# CPU-001.net
KiCad netlist of a schematic drawn in EAGLE
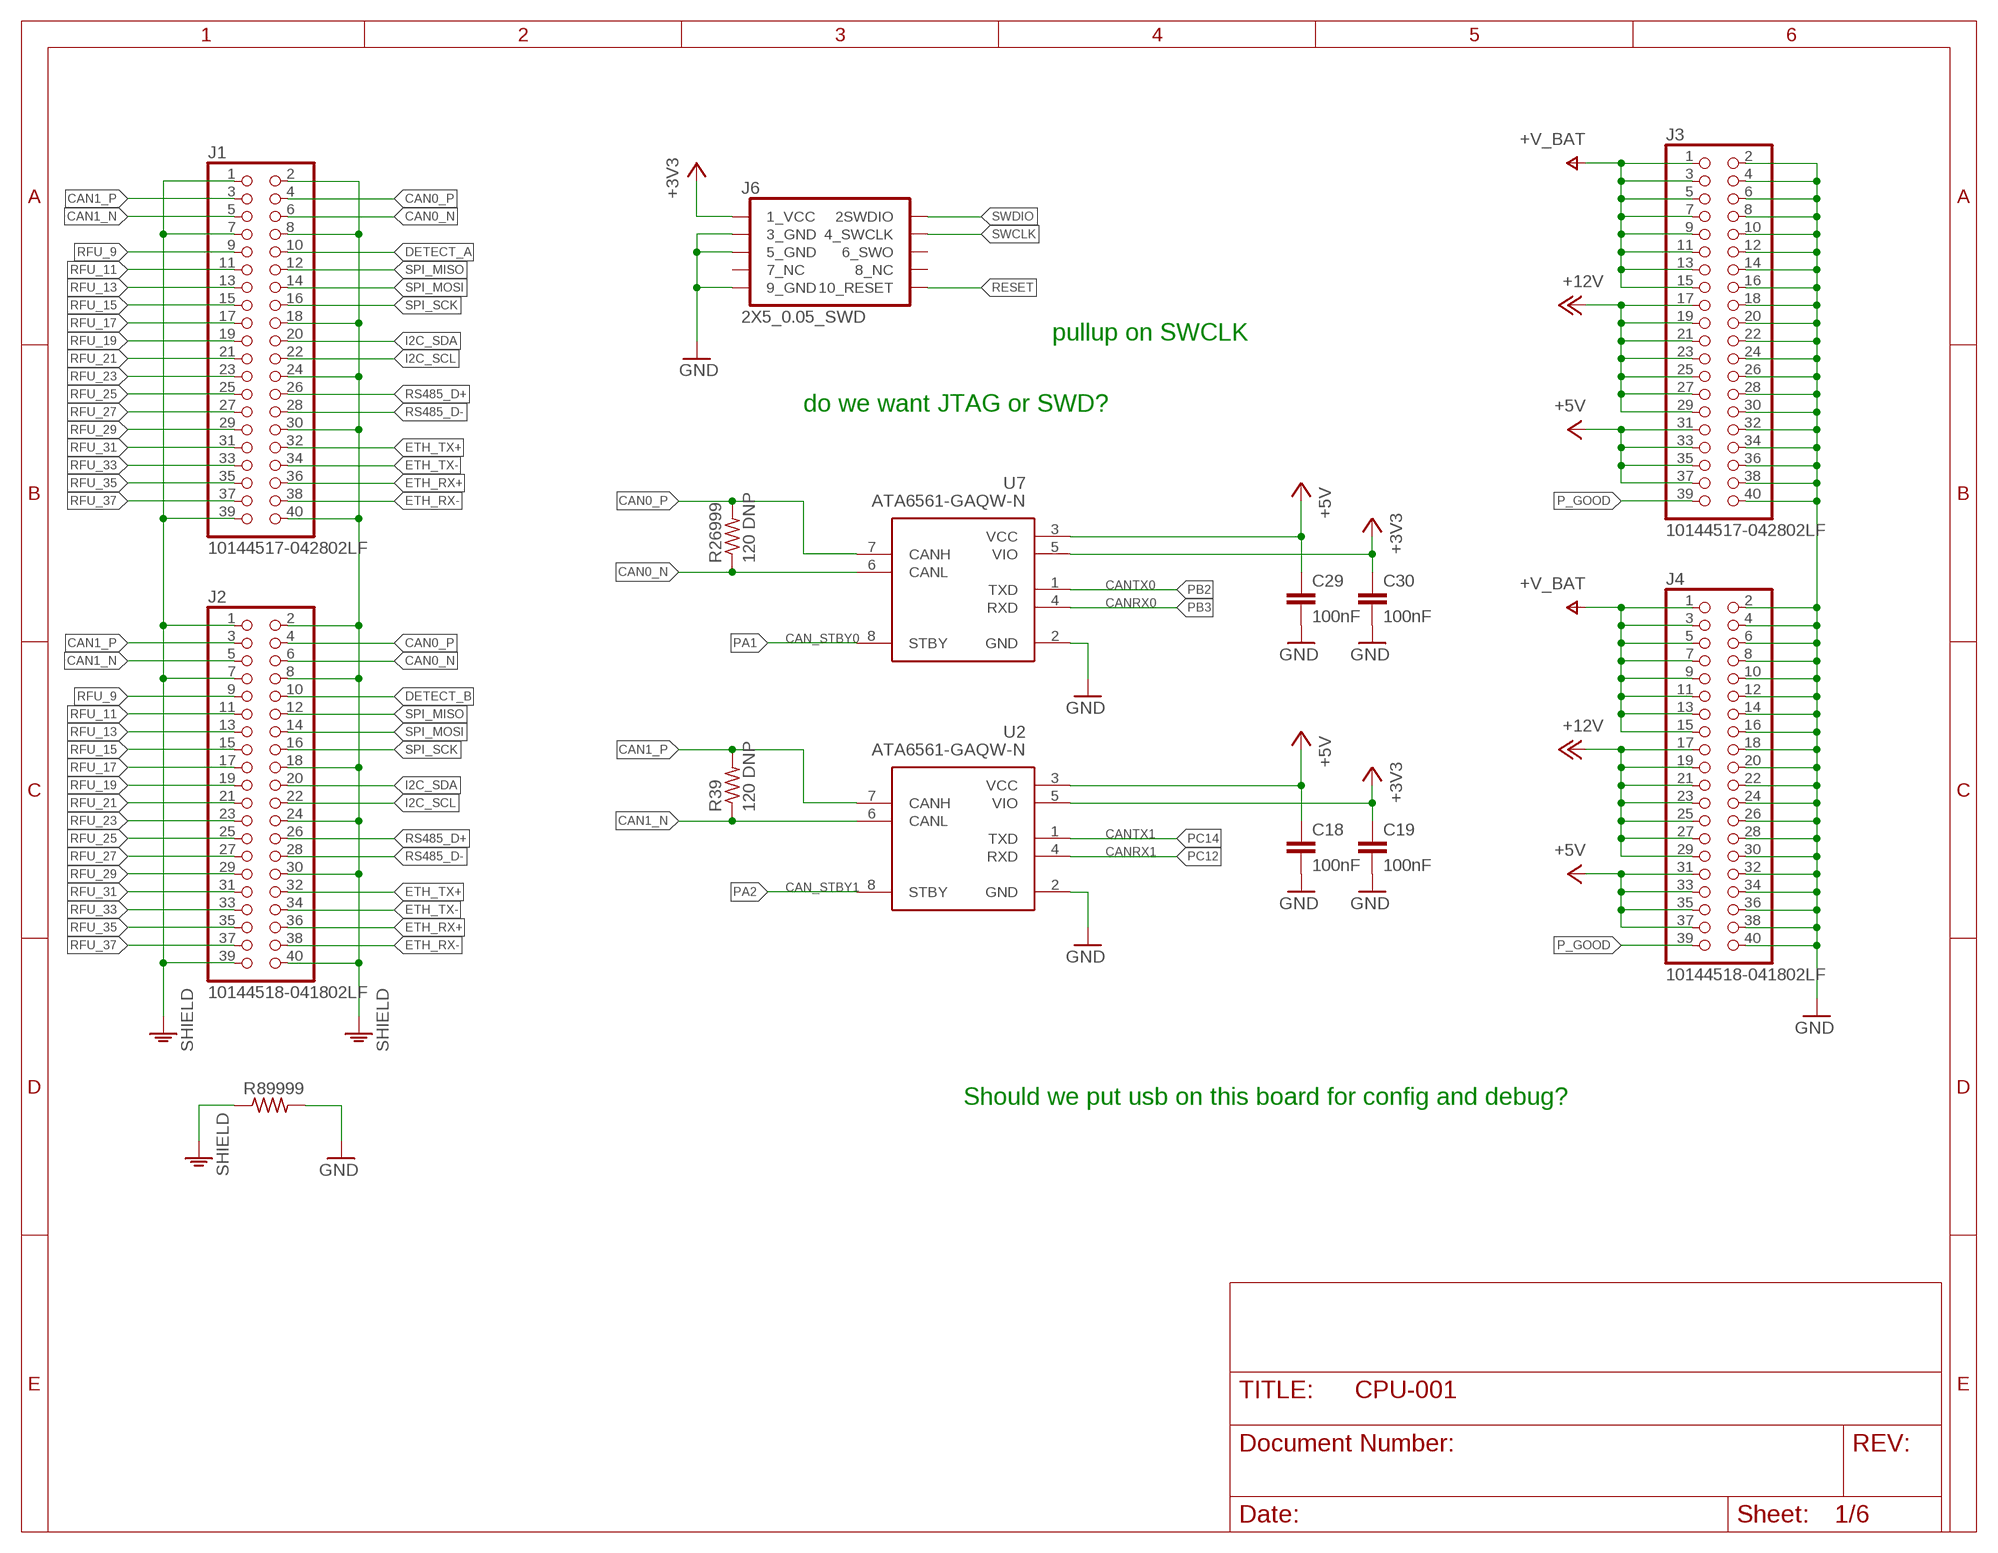
[diagram p0: schematic, sheet 1]
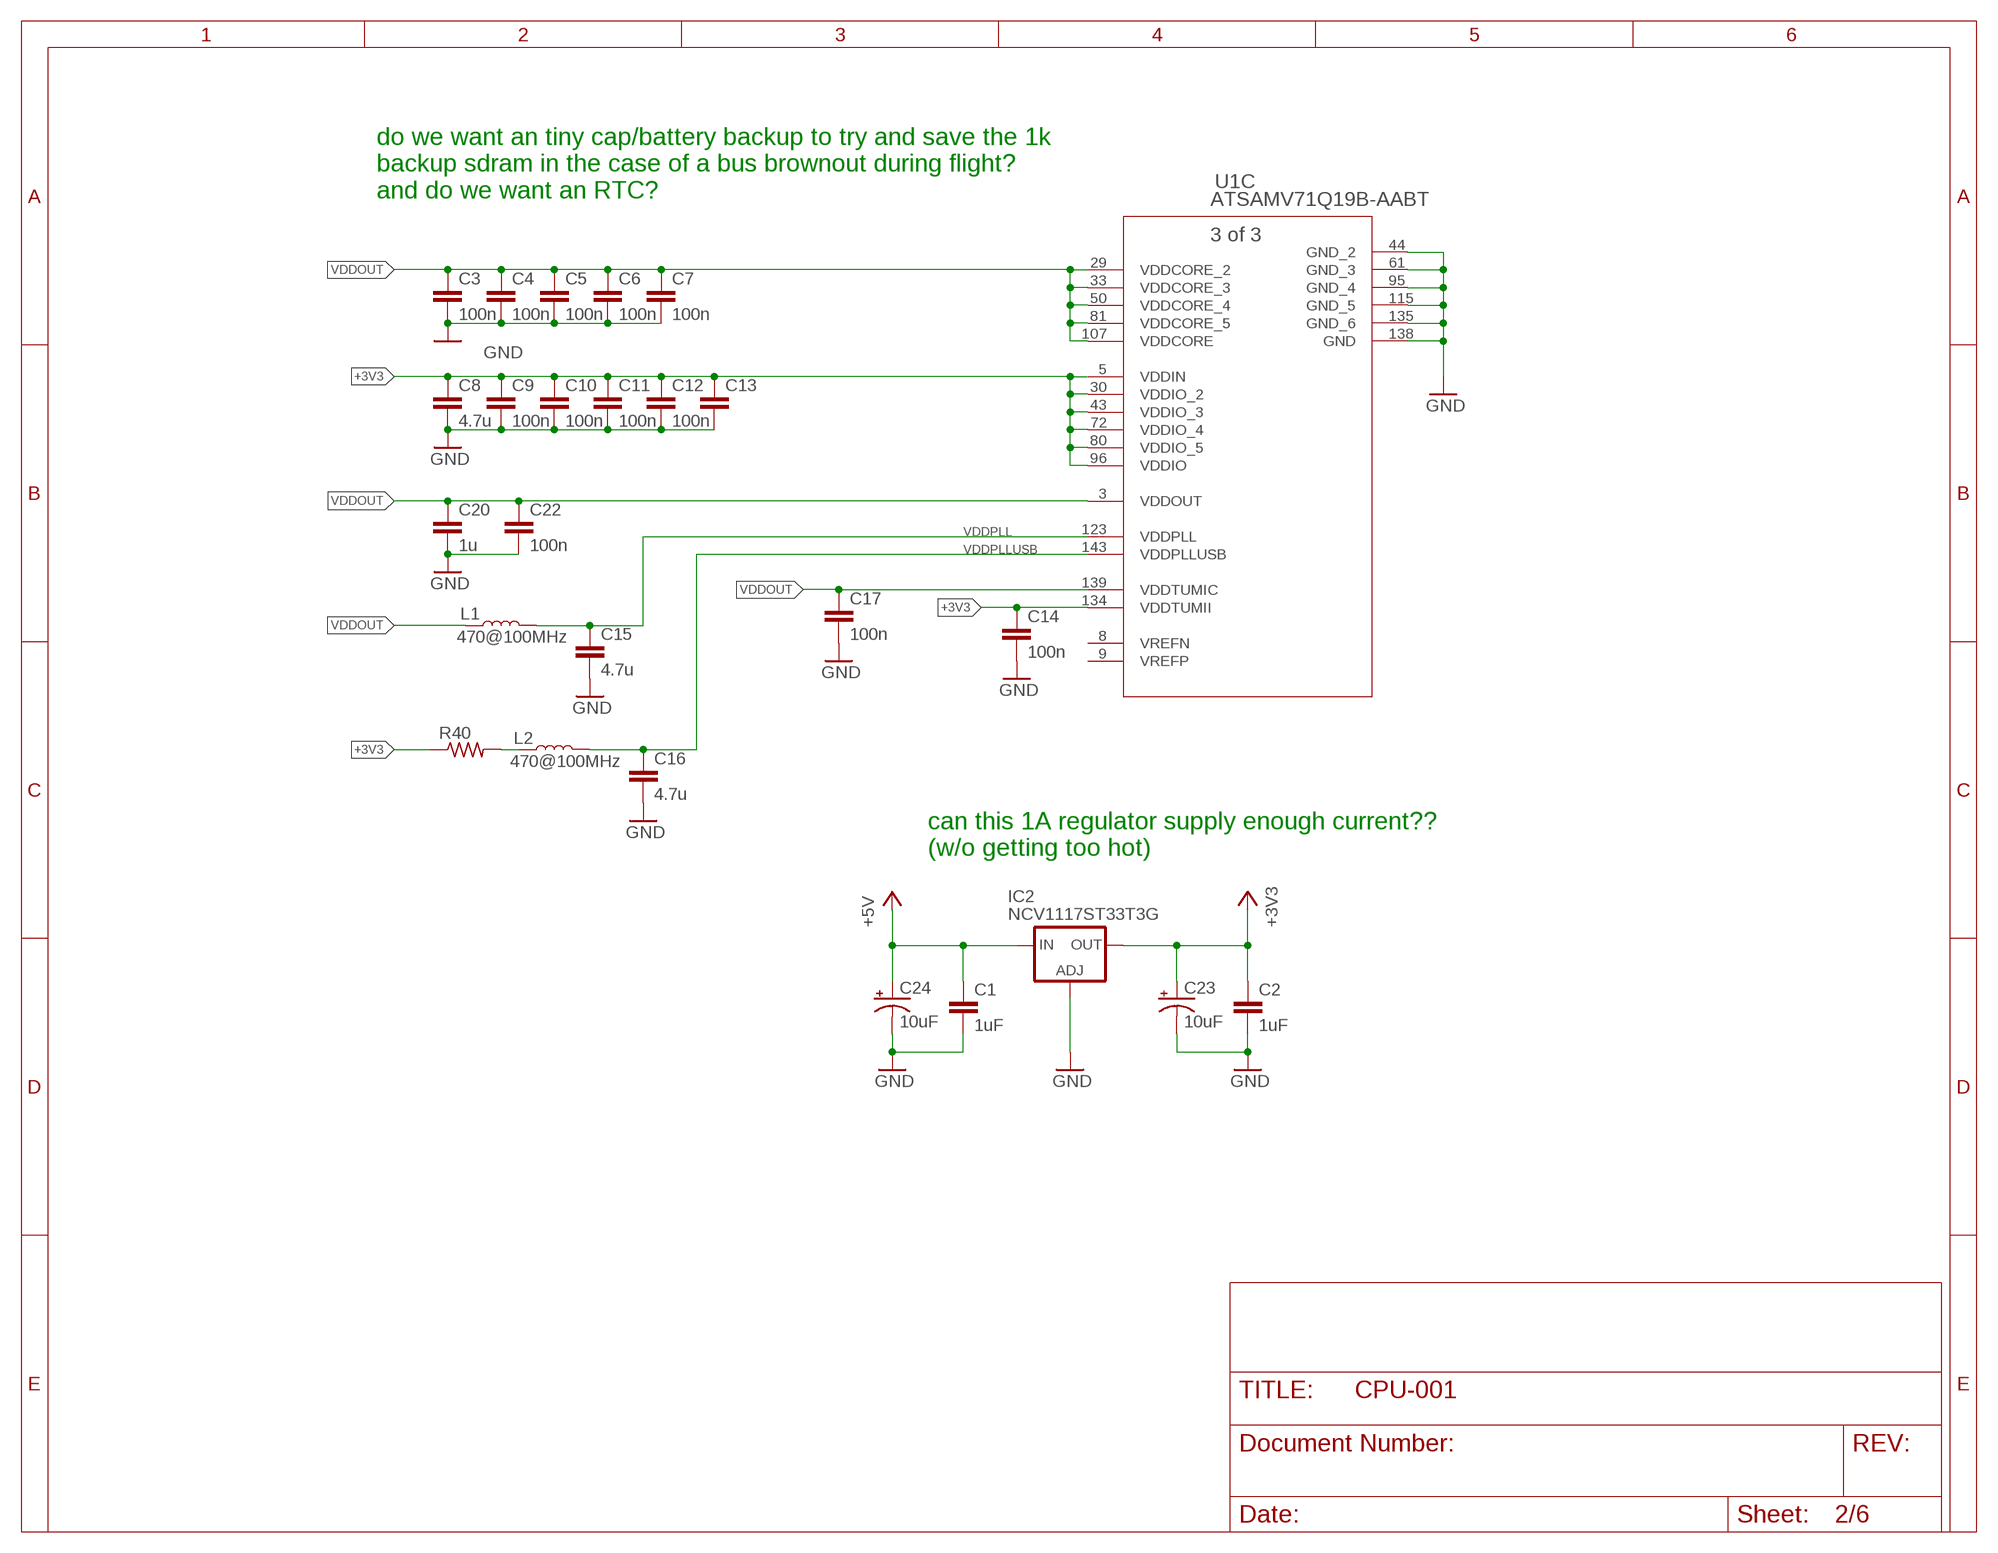
[diagram p1: schematic, sheet 2]
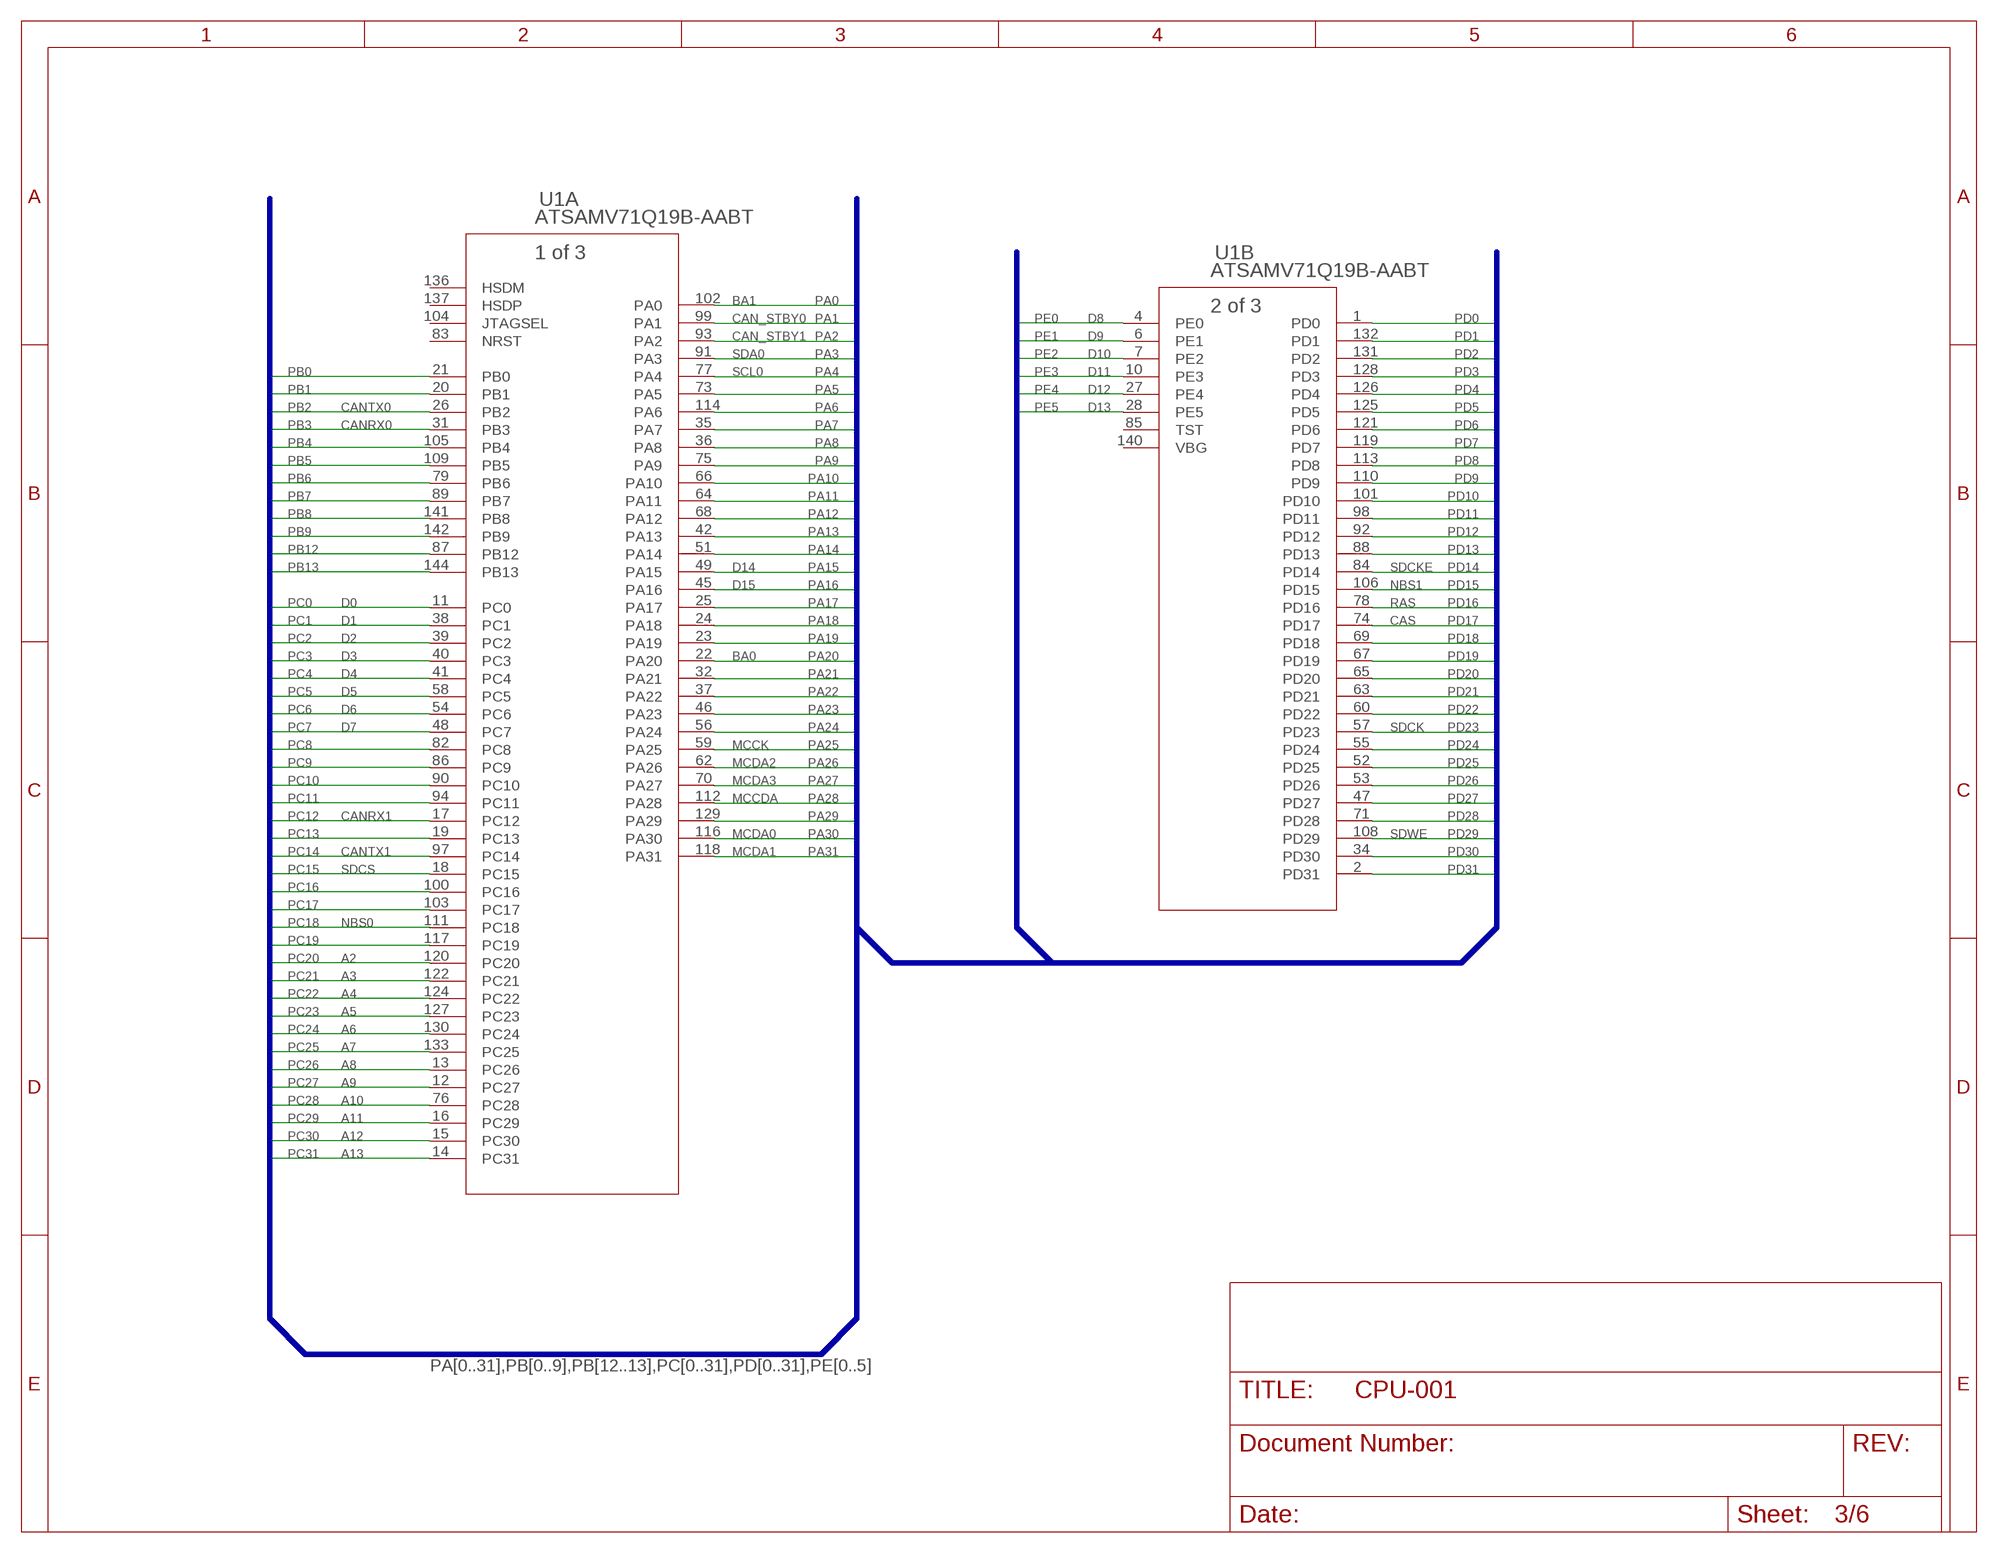
[diagram p2: schematic, sheet 3]
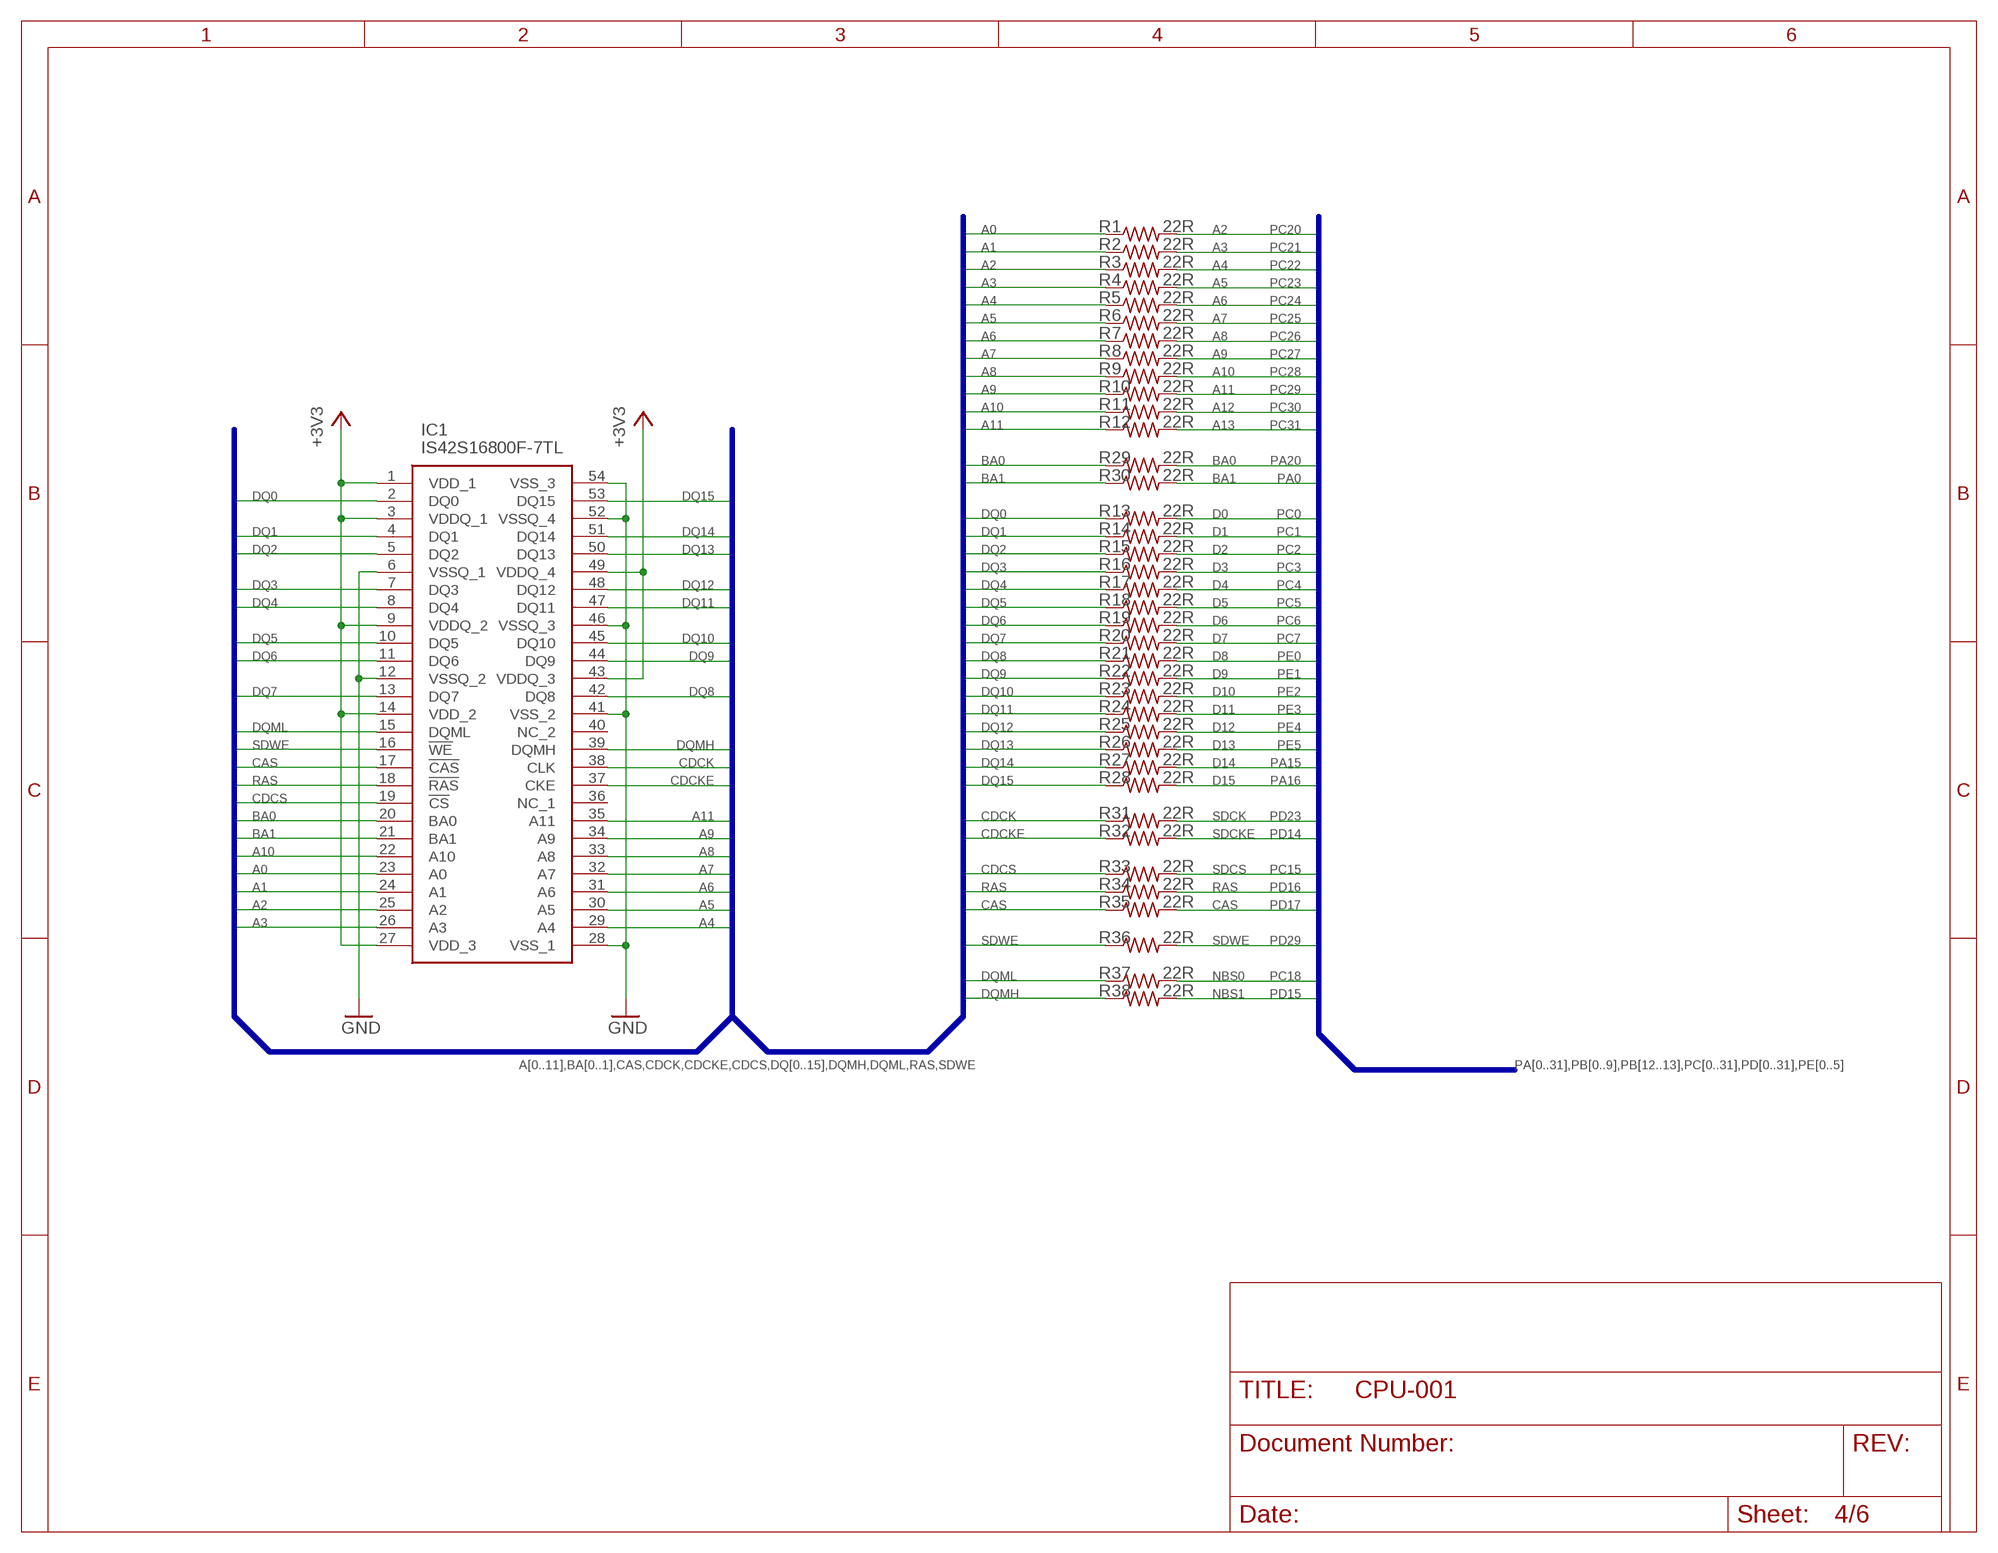
[diagram p3: schematic, sheet 4]
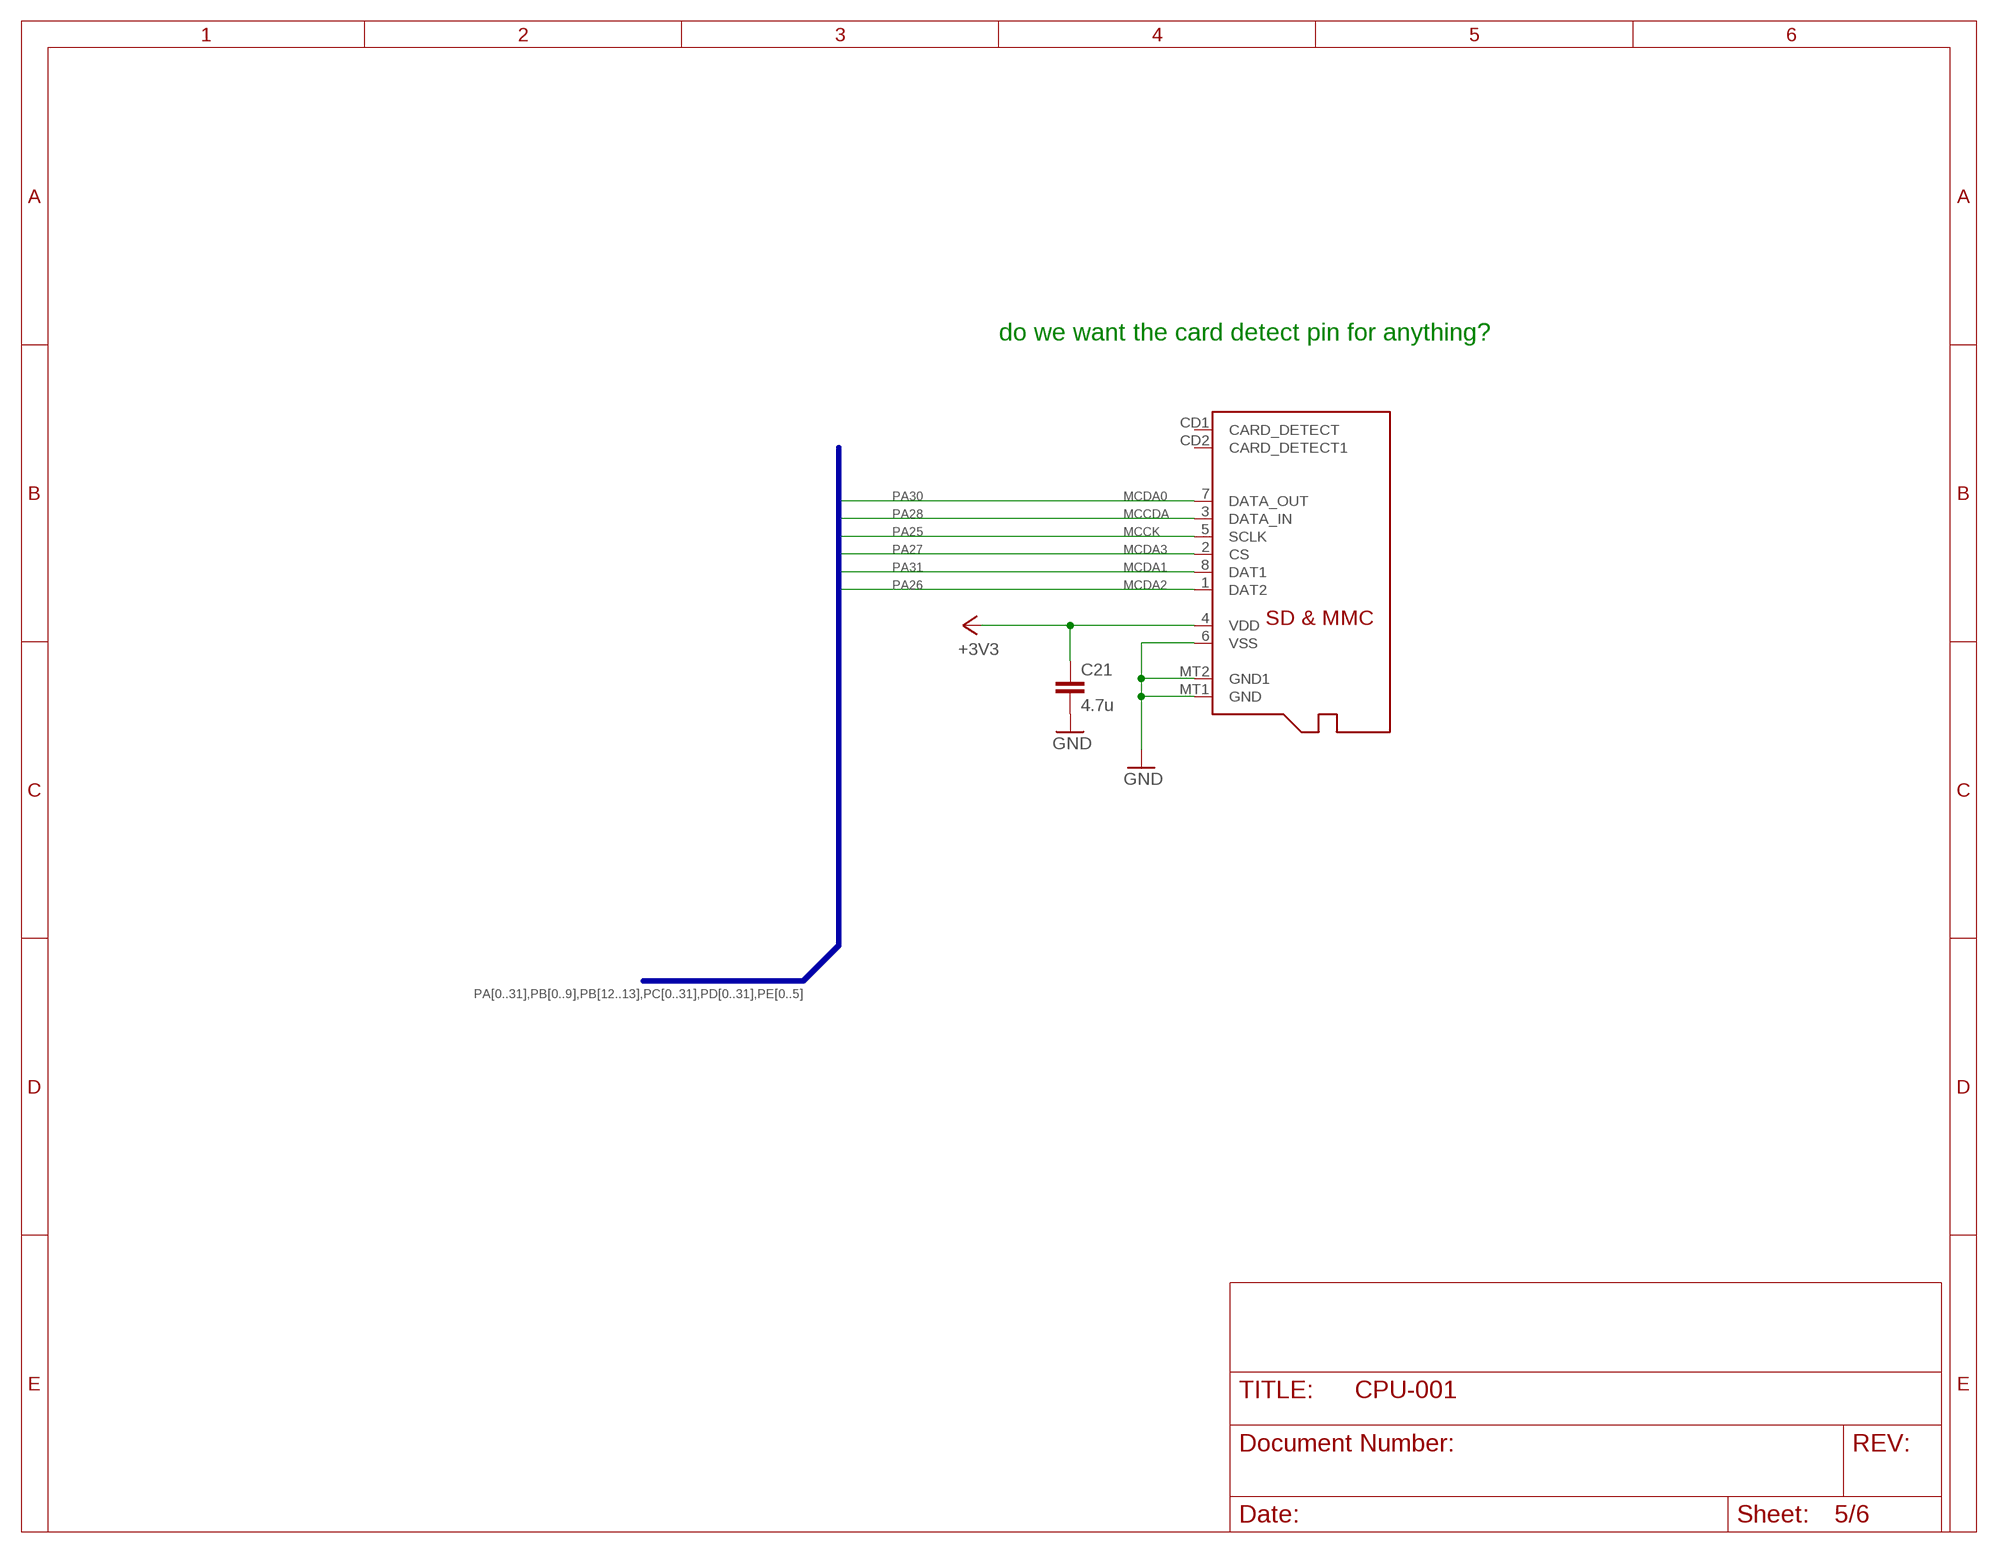
[diagram p4: schematic, sheet 5]
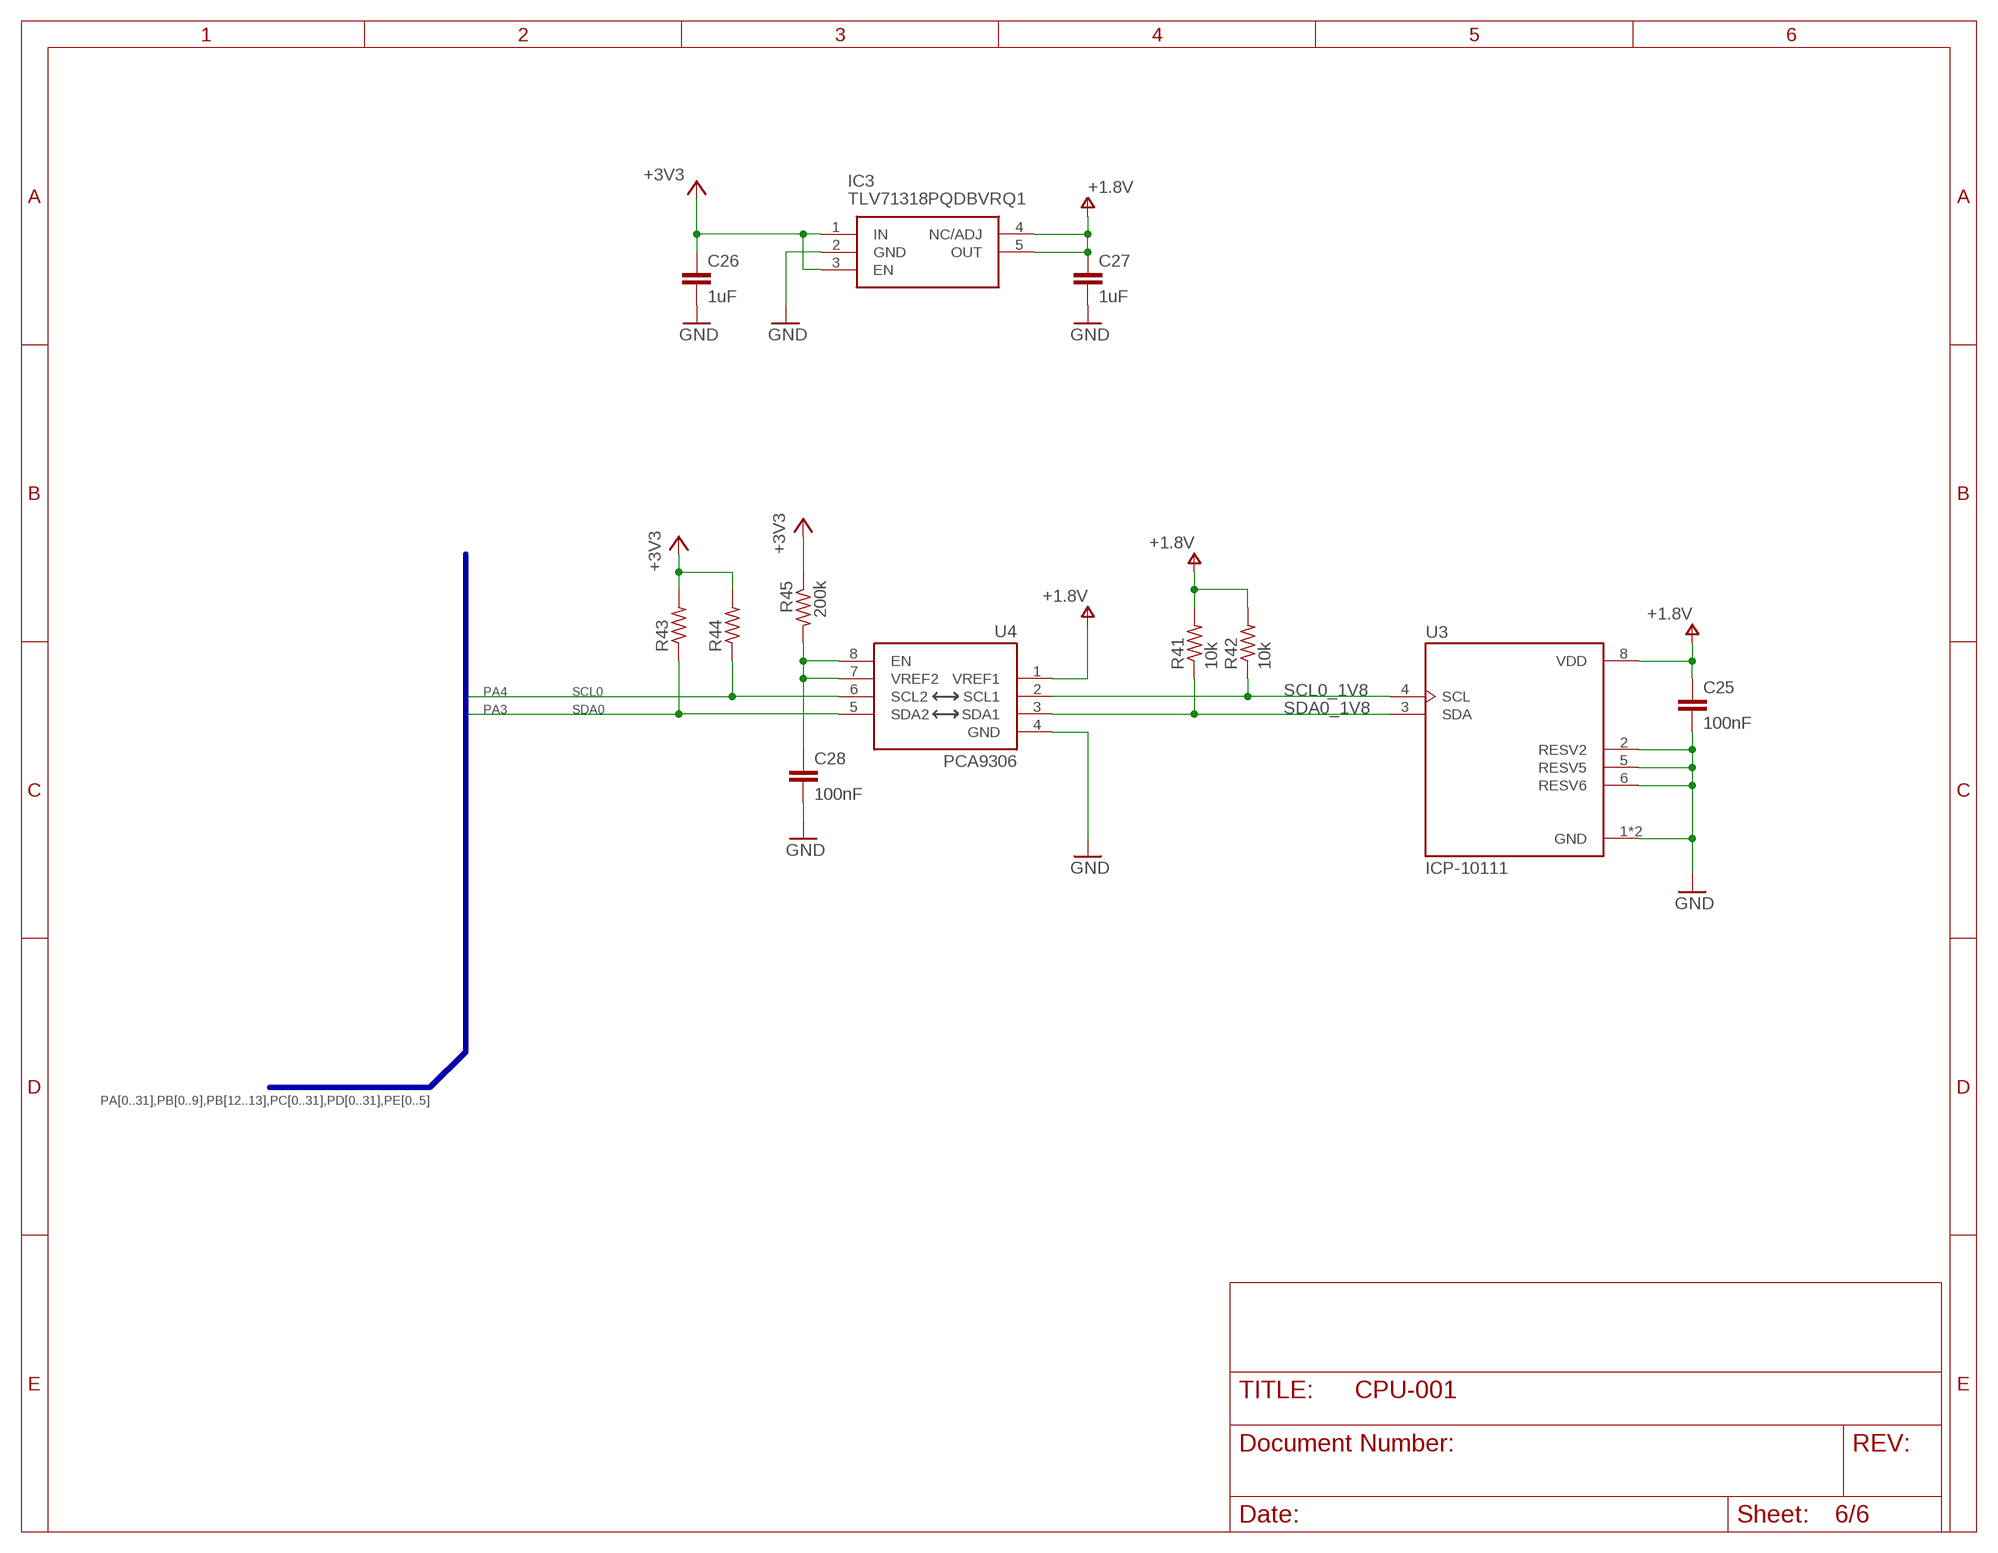
[diagram p5: schematic, sheet 6]

(export (version "E")
  (design (tool "Eeschema 10.0.6"))
  (components
    (comp (ref "U1")
      (value "ATSAMV71Q19B-AABT")
      (footprint "eagle-import:LQFP144_20X20MC")
      (fields (field (name "MANUFACTURER_PART_NUMBER") "ATSAMV71Q19BAABT"))
      (libsource (lib "eagle-import") (part "ATSAMV71Q19B-AABT"))
    )
    (comp (ref "C1")
      (value "1uF")
      (footprint "eagle-import:C0603")
      (libsource (lib "eagle-import") (part "C-EUC0603"))
    )
    (comp (ref "C2")
      (value "1uF")
      (footprint "eagle-import:C0603")
      (libsource (lib "eagle-import") (part "C-EUC0603"))
    )
    (comp (ref "C3")
      (value "100n")
      (footprint "eagle-import:C0402")
      (libsource (lib "eagle-import") (part "C-EUC0402"))
    )
    (comp (ref "C4")
      (value "100n")
      (footprint "eagle-import:C0402")
      (libsource (lib "eagle-import") (part "C-EUC0402"))
    )
    (comp (ref "C5")
      (value "100n")
      (footprint "eagle-import:C0402")
      (libsource (lib "eagle-import") (part "C-EUC0402"))
    )
    (comp (ref "C6")
      (value "100n")
      (footprint "eagle-import:C0402")
      (libsource (lib "eagle-import") (part "C-EUC0402"))
    )
    (comp (ref "C7")
      (value "100n")
      (footprint "eagle-import:C0402")
      (libsource (lib "eagle-import") (part "C-EUC0402"))
    )
    (comp (ref "C8")
      (value "4.7u")
      (footprint "eagle-import:C0805")
      (libsource (lib "eagle-import") (part "C-EUC0805"))
    )
    (comp (ref "C9")
      (value "100n")
      (footprint "eagle-import:C0402")
      (libsource (lib "eagle-import") (part "C-EUC0402"))
    )
    (comp (ref "C10")
      (value "100n")
      (footprint "eagle-import:C0402")
      (libsource (lib "eagle-import") (part "C-EUC0402"))
    )
    (comp (ref "C11")
      (value "100n")
      (footprint "eagle-import:C0402")
      (libsource (lib "eagle-import") (part "C-EUC0402"))
    )
    (comp (ref "C12")
      (value "100n")
      (footprint "eagle-import:C0402")
      (libsource (lib "eagle-import") (part "C-EUC0402"))
    )
    (comp (ref "C13")
      (value "100n")
      (footprint "eagle-import:C0402")
      (libsource (lib "eagle-import") (part "C-EUC0402"))
    )
    (comp (ref "C14")
      (value "100n")
      (footprint "eagle-import:C0402")
      (libsource (lib "eagle-import") (part "C-EUC0402"))
    )
    (comp (ref "C15")
      (value "4.7u")
      (footprint "eagle-import:C0805")
      (libsource (lib "eagle-import") (part "C-EUC0805"))
    )
    (comp (ref "C16")
      (value "4.7u")
      (footprint "eagle-import:C0805")
      (libsource (lib "eagle-import") (part "C-EUC0805"))
    )
    (comp (ref "C17")
      (value "100n")
      (footprint "eagle-import:C0402")
      (libsource (lib "eagle-import") (part "C-EUC0402"))
    )
    (comp (ref "C20")
      (value "1u")
      (footprint "eagle-import:C0402")
      (libsource (lib "eagle-import") (part "C-EUC0402"))
    )
    (comp (ref "C22")
      (value "100n")
      (footprint "eagle-import:C0402")
      (libsource (lib "eagle-import") (part "C-EUC0402"))
    )
    (comp (ref "C23")
      (value "10uF")
      (footprint "eagle-import:0603-POLAR")
      (libsource (lib "eagle-import") (part "10UF-POLAR-0603-6.3V-20%(TANT)"))
    )
    (comp (ref "C24")
      (value "10uF")
      (footprint "eagle-import:0603-POLAR")
      (libsource (lib "eagle-import") (part "10UF-POLAR-0603-6.3V-20%(TANT)"))
    )
    (comp (ref "IC2")
      (value "NCV1117ST33T3G")
      (footprint "eagle-import:SOT223")
      (libsource (lib "eagle-import") (part "LD117A?STR"))
    )
    (comp (ref "L1")
      (value "470@100MHz")
      (footprint "eagle-import:0603")
      (libsource (lib "eagle-import") (part "INDUCTOR-0603-33NH"))
    )
    (comp (ref "L2")
      (value "470@100MHz")
      (footprint "eagle-import:0603")
      (libsource (lib "eagle-import") (part "INDUCTOR-0603-33NH"))
    )
    (comp (ref "R40")
      (value "R-US_R0402")
      (footprint "eagle-import:R0402")
      (libsource (lib "eagle-import") (part "R-US_R0402"))
    )
    (comp (ref "C21")
      (value "4.7u")
      (footprint "eagle-import:C0805")
      (libsource (lib "eagle-import") (part "C-EUC0805"))
    )
    (comp (ref "U$5")
      (value "MICROSD")
      (footprint "eagle-import:MICROSD_")
      (libsource (lib "eagle-import") (part "MICROSD"))
    )
    (comp (ref "C18")
      (value "100nF")
      (footprint "eagle-import:C0402")
      (libsource (lib "eagle-import") (part "C-EUC0402"))
    )
    (comp (ref "C19")
      (value "100nF")
      (footprint "eagle-import:C0402")
      (libsource (lib "eagle-import") (part "C-EUC0402"))
    )
    (comp (ref "C29")
      (value "100nF")
      (footprint "eagle-import:C0402")
      (libsource (lib "eagle-import") (part "C-EUC0402"))
    )
    (comp (ref "C30")
      (value "100nF")
      (footprint "eagle-import:C0402")
      (libsource (lib "eagle-import") (part "C-EUC0402"))
    )
    (comp (ref "J1")
      (value "10144517-042802LF")
      (footprint "eagle-import:10144517-042802LF")
      (libsource (lib "eagle-import") (part "10144517-042802LF"))
    )
    (comp (ref "J2")
      (value "10144518-041802LF")
      (footprint "eagle-import:10144518-041802LF")
      (libsource (lib "eagle-import") (part "10144518-041802LF"))
    )
    (comp (ref "J3")
      (value "10144517-042802LF")
      (footprint "eagle-import:10144517-042802LF")
      (libsource (lib "eagle-import") (part "10144517-042802LF"))
    )
    (comp (ref "J4")
      (value "10144518-041802LF")
      (footprint "eagle-import:10144518-041802LF")
      (libsource (lib "eagle-import") (part "10144518-041802LF"))
    )
    (comp (ref "J6")
      (value "2X5_0.05_SWD")
      (footprint "eagle-import:2X5_RIGHT")
      (libsource (lib "eagle-import") (part "2X5_0.05_SWD"))
    )
    (comp (ref "R39")
      (value "120 DNP")
      (footprint "eagle-import:R0402")
      (libsource (lib "eagle-import") (part "R-US_R0402"))
    )
    (comp (ref "R26999")
      (value "120 DNP")
      (footprint "eagle-import:R0402")
      (libsource (lib "eagle-import") (part "R-US_R0402"))
    )
    (comp (ref "R89999")
      (value "R-US_R0402")
      (footprint "eagle-import:R0402")
      (libsource (lib "eagle-import") (part "R-US_R0402"))
    )
    (comp (ref "U2")
      (value "ATA6561-GAQW-N")
      (footprint "eagle-import:SOIC127P600X175-8N")
      (fields (field (name "MOUSER_PART_NUMBER") "579-ATA6561-GAQW-N"))
      (libsource (lib "eagle-import") (part "ATA6561-GAQW-N"))
    )
    (comp (ref "U7")
      (value "ATA6561-GAQW-N")
      (footprint "eagle-import:SOIC127P600X175-8N")
      (fields (field (name "MOUSER_PART_NUMBER") "579-ATA6561-GAQW-N"))
      (libsource (lib "eagle-import") (part "ATA6561-GAQW-N"))
    )
    (comp (ref "IC1")
      (value "IS42S16800F-7TL")
      (footprint "eagle-import:SOP80P1176X120-54N")
      (fields (field (name "MOUSER_PART_NUMBER") "870-IS42S16800F-7TL"))
      (libsource (lib "eagle-import") (part "IS42S16800F-7TL"))
    )
    (comp (ref "R1")
      (value "22R")
      (footprint "eagle-import:R0402")
      (libsource (lib "eagle-import") (part "R-US_R0402"))
    )
    (comp (ref "R2")
      (value "22R")
      (footprint "eagle-import:R0402")
      (libsource (lib "eagle-import") (part "R-US_R0402"))
    )
    (comp (ref "R3")
      (value "22R")
      (footprint "eagle-import:R0402")
      (libsource (lib "eagle-import") (part "R-US_R0402"))
    )
    (comp (ref "R4")
      (value "22R")
      (footprint "eagle-import:R0402")
      (libsource (lib "eagle-import") (part "R-US_R0402"))
    )
    (comp (ref "R5")
      (value "22R")
      (footprint "eagle-import:R0402")
      (libsource (lib "eagle-import") (part "R-US_R0402"))
    )
    (comp (ref "R6")
      (value "22R")
      (footprint "eagle-import:R0402")
      (libsource (lib "eagle-import") (part "R-US_R0402"))
    )
    (comp (ref "R7")
      (value "22R")
      (footprint "eagle-import:R0402")
      (libsource (lib "eagle-import") (part "R-US_R0402"))
    )
    (comp (ref "R8")
      (value "22R")
      (footprint "eagle-import:R0402")
      (libsource (lib "eagle-import") (part "R-US_R0402"))
    )
    (comp (ref "R9")
      (value "22R")
      (footprint "eagle-import:R0402")
      (libsource (lib "eagle-import") (part "R-US_R0402"))
    )
    (comp (ref "R10")
      (value "22R")
      (footprint "eagle-import:R0402")
      (libsource (lib "eagle-import") (part "R-US_R0402"))
    )
    (comp (ref "R11")
      (value "22R")
      (footprint "eagle-import:R0402")
      (libsource (lib "eagle-import") (part "R-US_R0402"))
    )
    (comp (ref "R12")
      (value "22R")
      (footprint "eagle-import:R0402")
      (libsource (lib "eagle-import") (part "R-US_R0402"))
    )
    (comp (ref "R13")
      (value "22R")
      (footprint "eagle-import:R0402")
      (libsource (lib "eagle-import") (part "R-US_R0402"))
    )
    (comp (ref "R14")
      (value "22R")
      (footprint "eagle-import:R0402")
      (libsource (lib "eagle-import") (part "R-US_R0402"))
    )
    (comp (ref "R15")
      (value "22R")
      (footprint "eagle-import:R0402")
      (libsource (lib "eagle-import") (part "R-US_R0402"))
    )
    (comp (ref "R16")
      (value "22R")
      (footprint "eagle-import:R0402")
      (libsource (lib "eagle-import") (part "R-US_R0402"))
    )
    (comp (ref "R17")
      (value "22R")
      (footprint "eagle-import:R0402")
      (libsource (lib "eagle-import") (part "R-US_R0402"))
    )
    (comp (ref "R18")
      (value "22R")
      (footprint "eagle-import:R0402")
      (libsource (lib "eagle-import") (part "R-US_R0402"))
    )
    (comp (ref "R19")
      (value "22R")
      (footprint "eagle-import:R0402")
      (libsource (lib "eagle-import") (part "R-US_R0402"))
    )
    (comp (ref "R20")
      (value "22R")
      (footprint "eagle-import:R0402")
      (libsource (lib "eagle-import") (part "R-US_R0402"))
    )
    (comp (ref "R21")
      (value "22R")
      (footprint "eagle-import:R0402")
      (libsource (lib "eagle-import") (part "R-US_R0402"))
    )
    (comp (ref "R22")
      (value "22R")
      (footprint "eagle-import:R0402")
      (libsource (lib "eagle-import") (part "R-US_R0402"))
    )
    (comp (ref "R23")
      (value "22R")
      (footprint "eagle-import:R0402")
      (libsource (lib "eagle-import") (part "R-US_R0402"))
    )
    (comp (ref "R24")
      (value "22R")
      (footprint "eagle-import:R0402")
      (libsource (lib "eagle-import") (part "R-US_R0402"))
    )
    (comp (ref "R25")
      (value "22R")
      (footprint "eagle-import:R0402")
      (libsource (lib "eagle-import") (part "R-US_R0402"))
    )
    (comp (ref "R26")
      (value "22R")
      (footprint "eagle-import:R0402")
      (libsource (lib "eagle-import") (part "R-US_R0402"))
    )
    (comp (ref "R27")
      (value "22R")
      (footprint "eagle-import:R0402")
      (libsource (lib "eagle-import") (part "R-US_R0402"))
    )
    (comp (ref "R28")
      (value "22R")
      (footprint "eagle-import:R0402")
      (libsource (lib "eagle-import") (part "R-US_R0402"))
    )
    (comp (ref "R29")
      (value "22R")
      (footprint "eagle-import:R0402")
      (libsource (lib "eagle-import") (part "R-US_R0402"))
    )
    (comp (ref "R30")
      (value "22R")
      (footprint "eagle-import:R0402")
      (libsource (lib "eagle-import") (part "R-US_R0402"))
    )
    (comp (ref "R31")
      (value "22R")
      (footprint "eagle-import:R0402")
      (libsource (lib "eagle-import") (part "R-US_R0402"))
    )
    (comp (ref "R32")
      (value "22R")
      (footprint "eagle-import:R0402")
      (libsource (lib "eagle-import") (part "R-US_R0402"))
    )
    (comp (ref "R33")
      (value "22R")
      (footprint "eagle-import:R0402")
      (libsource (lib "eagle-import") (part "R-US_R0402"))
    )
    (comp (ref "R34")
      (value "22R")
      (footprint "eagle-import:R0402")
      (libsource (lib "eagle-import") (part "R-US_R0402"))
    )
    (comp (ref "R35")
      (value "22R")
      (footprint "eagle-import:R0402")
      (libsource (lib "eagle-import") (part "R-US_R0402"))
    )
    (comp (ref "R36")
      (value "22R")
      (footprint "eagle-import:R0402")
      (libsource (lib "eagle-import") (part "R-US_R0402"))
    )
    (comp (ref "R37")
      (value "22R")
      (footprint "eagle-import:R0402")
      (libsource (lib "eagle-import") (part "R-US_R0402"))
    )
    (comp (ref "R38")
      (value "22R")
      (footprint "eagle-import:R0402")
      (libsource (lib "eagle-import") (part "R-US_R0402"))
    )
    (comp (ref "C25")
      (value "100nF")
      (footprint "eagle-import:C0402")
      (libsource (lib "eagle-import") (part "C-EUC0402"))
    )
    (comp (ref "C26")
      (value "1uF")
      (footprint "eagle-import:C0402")
      (libsource (lib "eagle-import") (part "C-EUC0402"))
    )
    (comp (ref "C27")
      (value "1uF")
      (footprint "eagle-import:C0402")
      (libsource (lib "eagle-import") (part "C-EUC0402"))
    )
    (comp (ref "C28")
      (value "100nF")
      (footprint "eagle-import:C0402")
      (libsource (lib "eagle-import") (part "C-EUC0402"))
    )
    (comp (ref "IC3")
      (value "TLV71318PQDBVRQ1")
      (footprint "eagle-import:SOT95P280X100-5N")
      (fields
        (field (name "MANUFACTURER_PART_NUMBER") "NCP718BSN180T1G")
        (field (name "MOUSER_PART_NUMBER") "863-NCP718BSN180T1G")
      )
      (libsource (lib "eagle-import") (part "NCP718BSN180T1G"))
    )
    (comp (ref "R41")
      (value "10k")
      (footprint "eagle-import:R0402")
      (libsource (lib "eagle-import") (part "R-US_R0402"))
    )
    (comp (ref "R42")
      (value "10k")
      (footprint "eagle-import:R0402")
      (libsource (lib "eagle-import") (part "R-US_R0402"))
    )
    (comp (ref "R43")
      (value "R-US_R0402")
      (footprint "eagle-import:R0402")
      (libsource (lib "eagle-import") (part "R-US_R0402"))
    )
    (comp (ref "R44")
      (value "R-US_R0402")
      (footprint "eagle-import:R0402")
      (libsource (lib "eagle-import") (part "R-US_R0402"))
    )
    (comp (ref "R45")
      (value "200k")
      (footprint "eagle-import:R0402")
      (libsource (lib "eagle-import") (part "R-US_R0402"))
    )
    (comp (ref "U3")
      (value "ICP-10111")
      (footprint "eagle-import:PSON65P250X200X100-8N")
      (fields (field (name "DIGI-KEY_PART_NUMBER") "1428-1145-1-ND") (field (name "MF") "TDK InvenSense"))
      (libsource (lib "eagle-import") (part "ICP-10111"))
    )
    (comp (ref "U4")
      (value "PCA9306")
      (footprint "eagle-import:PCA9306DC")
      (libsource (lib "eagle-import") (part "PCA9306PCA9306DC-1{colon}1"))
    )
  )
  (nets
    (net (code "1") (name "+1.8V") (class "Default")
      (node (ref "C25") (pin "1") (pinfunction "1_1") (pintype "passive"))
      (node (ref "C27") (pin "1") (pinfunction "1_1") (pintype "passive"))
      (node (ref "IC3") (pin "4") (pinfunction "NC/ADJ_4") (pintype "bidirectional"))
      (node (ref "IC3") (pin "5") (pinfunction "OUT_5") (pintype "bidirectional"))
      (node (ref "R41") (pin "2") (pinfunction "2_2") (pintype "passive"))
      (node (ref "R42") (pin "2") (pinfunction "2_2") (pintype "passive"))
      (node (ref "U3") (pin "8") (pinfunction "VDD_8") (pintype "power_in"))
      (node (ref "U4") (pin "1") (pinfunction "VREF1_1") (pintype "bidirectional"))
    )
    (net (code "2") (name "+3V3") (class "Default")
      (node (ref "C10") (pin "1") (pinfunction "1_1") (pintype "passive"))
      (node (ref "C11") (pin "1") (pinfunction "1_1") (pintype "passive"))
      (node (ref "C12") (pin "1") (pinfunction "1_1") (pintype "passive"))
      (node (ref "C13") (pin "1") (pinfunction "1_1") (pintype "passive"))
      (node (ref "C14") (pin "1") (pinfunction "1_1") (pintype "passive"))
      (node (ref "C19") (pin "1") (pinfunction "1_1") (pintype "passive"))
      (node (ref "C2") (pin "1") (pinfunction "1_1") (pintype "passive"))
      (node (ref "C21") (pin "1") (pinfunction "1_1") (pintype "passive"))
      (node (ref "C23") (pin "+") (pinfunction "+_+") (pintype "passive"))
      (node (ref "C26") (pin "1") (pinfunction "1_1") (pintype "passive"))
      (node (ref "C30") (pin "1") (pinfunction "1_1") (pintype "passive"))
      (node (ref "C8") (pin "1") (pinfunction "1_1") (pintype "passive"))
      (node (ref "C9") (pin "1") (pinfunction "1_1") (pintype "passive"))
      (node (ref "IC1") (pin "1") (pinfunction "VDD_1_1") (pintype "bidirectional"))
      (node (ref "IC1") (pin "14") (pinfunction "VDD_2_14") (pintype "bidirectional"))
      (node (ref "IC1") (pin "27") (pinfunction "VDD_3_27") (pintype "bidirectional"))
      (node (ref "IC1") (pin "3") (pinfunction "VDDQ_1_3") (pintype "bidirectional"))
      (node (ref "IC1") (pin "43") (pinfunction "VDDQ_3_43") (pintype "bidirectional"))
      (node (ref "IC1") (pin "49") (pinfunction "VDDQ_4_49") (pintype "bidirectional"))
      (node (ref "IC1") (pin "9") (pinfunction "VDDQ_2_9") (pintype "bidirectional"))
      (node (ref "IC2") (pin "4") (pinfunction "OUT_4") (pintype "passive"))
      (node (ref "IC3") (pin "1") (pinfunction "IN_1") (pintype "bidirectional"))
      (node (ref "IC3") (pin "3") (pinfunction "EN_3") (pintype "bidirectional"))
      (node (ref "J6") (pin "1") (pinfunction "1_VCC_1") (pintype "passive"))
      (node (ref "R40") (pin "1") (pinfunction "1_1") (pintype "passive"))
      (node (ref "R43") (pin "2") (pinfunction "2_2") (pintype "passive"))
      (node (ref "R44") (pin "2") (pinfunction "2_2") (pintype "passive"))
      (node (ref "R45") (pin "1") (pinfunction "1_1") (pintype "passive"))
      (node (ref "U$5") (pin "4") (pinfunction "VDD_4") (pintype "power_in"))
      (node (ref "U1") (pin "134") (pinfunction "VDDTUMII_134") (pintype "power_in"))
      (node (ref "U1") (pin "30") (pinfunction "VDDIO_2_30") (pintype "power_in"))
      (node (ref "U1") (pin "43") (pinfunction "VDDIO_3_43") (pintype "power_in"))
      (node (ref "U1") (pin "5") (pinfunction "VDDIN_5") (pintype "power_in"))
      (node (ref "U1") (pin "72") (pinfunction "VDDIO_4_72") (pintype "power_in"))
      (node (ref "U1") (pin "80") (pinfunction "VDDIO_5_80") (pintype "power_in"))
      (node (ref "U1") (pin "96") (pinfunction "VDDIO_96") (pintype "power_in"))
      (node (ref "U2") (pin "5") (pinfunction "VIO_5") (pintype "bidirectional"))
      (node (ref "U7") (pin "5") (pinfunction "VIO_5") (pintype "bidirectional"))
    )
    (net (code "3") (name "+5V") (class "Default")
      (node (ref "C1") (pin "1") (pinfunction "1_1") (pintype "passive"))
      (node (ref "C18") (pin "1") (pinfunction "1_1") (pintype "passive"))
      (node (ref "C24") (pin "+") (pinfunction "+_+") (pintype "passive"))
      (node (ref "C29") (pin "1") (pinfunction "1_1") (pintype "passive"))
      (node (ref "IC2") (pin "3") (pinfunction "IN_3") (pintype "input"))
      (node (ref "J3") (pin "31") (pinfunction "31_31") (pintype "passive"))
      (node (ref "J3") (pin "33") (pinfunction "33_33") (pintype "passive"))
      (node (ref "J3") (pin "35") (pinfunction "35_35") (pintype "passive"))
      (node (ref "J3") (pin "37") (pinfunction "37_37") (pintype "passive"))
      (node (ref "J4") (pin "31") (pinfunction "31_31") (pintype "passive"))
      (node (ref "J4") (pin "33") (pinfunction "33_33") (pintype "passive"))
      (node (ref "J4") (pin "35") (pinfunction "35_35") (pintype "passive"))
      (node (ref "J4") (pin "37") (pinfunction "37_37") (pintype "passive"))
      (node (ref "U2") (pin "3") (pinfunction "VCC_3") (pintype "bidirectional"))
      (node (ref "U7") (pin "3") (pinfunction "VCC_3") (pintype "bidirectional"))
    )
    (net (code "4") (name "+12V") (class "Default")
      (node (ref "J3") (pin "17") (pinfunction "17_17") (pintype "passive"))
      (node (ref "J3") (pin "19") (pinfunction "19_19") (pintype "passive"))
      (node (ref "J3") (pin "21") (pinfunction "21_21") (pintype "passive"))
      (node (ref "J3") (pin "23") (pinfunction "23_23") (pintype "passive"))
      (node (ref "J3") (pin "25") (pinfunction "25_25") (pintype "passive"))
      (node (ref "J3") (pin "27") (pinfunction "27_27") (pintype "passive"))
      (node (ref "J3") (pin "29") (pinfunction "29_29") (pintype "passive"))
      (node (ref "J4") (pin "17") (pinfunction "17_17") (pintype "passive"))
      (node (ref "J4") (pin "19") (pinfunction "19_19") (pintype "passive"))
      (node (ref "J4") (pin "21") (pinfunction "21_21") (pintype "passive"))
      (node (ref "J4") (pin "23") (pinfunction "23_23") (pintype "passive"))
      (node (ref "J4") (pin "25") (pinfunction "25_25") (pintype "passive"))
      (node (ref "J4") (pin "27") (pinfunction "27_27") (pintype "passive"))
      (node (ref "J4") (pin "29") (pinfunction "29_29") (pintype "passive"))
    )
    (net (code "5") (name "+V_BAT") (class "Default")
      (node (ref "J3") (pin "1") (pinfunction "1_1") (pintype "passive"))
      (node (ref "J3") (pin "11") (pinfunction "11_11") (pintype "passive"))
      (node (ref "J3") (pin "13") (pinfunction "13_13") (pintype "passive"))
      (node (ref "J3") (pin "15") (pinfunction "15_15") (pintype "passive"))
      (node (ref "J3") (pin "3") (pinfunction "3_3") (pintype "passive"))
      (node (ref "J3") (pin "5") (pinfunction "5_5") (pintype "passive"))
      (node (ref "J3") (pin "7") (pinfunction "7_7") (pintype "passive"))
      (node (ref "J3") (pin "9") (pinfunction "9_9") (pintype "passive"))
      (node (ref "J4") (pin "1") (pinfunction "1_1") (pintype "passive"))
      (node (ref "J4") (pin "11") (pinfunction "11_11") (pintype "passive"))
      (node (ref "J4") (pin "13") (pinfunction "13_13") (pintype "passive"))
      (node (ref "J4") (pin "15") (pinfunction "15_15") (pintype "passive"))
      (node (ref "J4") (pin "3") (pinfunction "3_3") (pintype "passive"))
      (node (ref "J4") (pin "5") (pinfunction "5_5") (pintype "passive"))
      (node (ref "J4") (pin "7") (pinfunction "7_7") (pintype "passive"))
      (node (ref "J4") (pin "9") (pinfunction "9_9") (pintype "passive"))
    )
    (net (code "11") (name "A0") (class "Default")
      (node (ref "IC1") (pin "23") (pinfunction "A0_23") (pintype "bidirectional"))
      (node (ref "R1") (pin "1") (pinfunction "1_1") (pintype "passive"))
    )
    (net (code "12") (name "A1") (class "Default")
      (node (ref "IC1") (pin "24") (pinfunction "A1_24") (pintype "bidirectional"))
      (node (ref "R2") (pin "1") (pinfunction "1_1") (pintype "passive"))
    )
    (net (code "13") (name "A2") (class "Default")
      (node (ref "IC1") (pin "25") (pinfunction "A2_25") (pintype "bidirectional"))
      (node (ref "R3") (pin "1") (pinfunction "1_1") (pintype "passive"))
    )
    (net (code "14") (name "A3") (class "Default")
      (node (ref "IC1") (pin "26") (pinfunction "A3_26") (pintype "bidirectional"))
      (node (ref "R4") (pin "1") (pinfunction "1_1") (pintype "passive"))
    )
    (net (code "15") (name "A4") (class "Default")
      (node (ref "IC1") (pin "29") (pinfunction "A4_29") (pintype "bidirectional"))
      (node (ref "R5") (pin "1") (pinfunction "1_1") (pintype "passive"))
    )
    (net (code "16") (name "A5") (class "Default")
      (node (ref "IC1") (pin "30") (pinfunction "A5_30") (pintype "bidirectional"))
      (node (ref "R6") (pin "1") (pinfunction "1_1") (pintype "passive"))
    )
    (net (code "17") (name "A6") (class "Default")
      (node (ref "IC1") (pin "31") (pinfunction "A6_31") (pintype "bidirectional"))
      (node (ref "R7") (pin "1") (pinfunction "1_1") (pintype "passive"))
    )
    (net (code "18") (name "A7") (class "Default")
      (node (ref "IC1") (pin "32") (pinfunction "A7_32") (pintype "bidirectional"))
      (node (ref "R8") (pin "1") (pinfunction "1_1") (pintype "passive"))
    )
    (net (code "19") (name "A8") (class "Default")
      (node (ref "IC1") (pin "33") (pinfunction "A8_33") (pintype "bidirectional"))
      (node (ref "R9") (pin "1") (pinfunction "1_1") (pintype "passive"))
    )
    (net (code "20") (name "A9") (class "Default")
      (node (ref "IC1") (pin "34") (pinfunction "A9_34") (pintype "bidirectional"))
      (node (ref "R10") (pin "1") (pinfunction "1_1") (pintype "passive"))
    )
    (net (code "21") (name "A10") (class "Default")
      (node (ref "IC1") (pin "22") (pinfunction "A10_22") (pintype "bidirectional"))
      (node (ref "R11") (pin "1") (pinfunction "1_1") (pintype "passive"))
    )
    (net (code "22") (name "A11") (class "Default")
      (node (ref "IC1") (pin "35") (pinfunction "A11_35") (pintype "bidirectional"))
      (node (ref "R12") (pin "1") (pinfunction "1_1") (pintype "passive"))
    )
    (net (code "23") (name "BA0") (class "Default")
      (node (ref "IC1") (pin "20") (pinfunction "BA0_20") (pintype "bidirectional"))
      (node (ref "R29") (pin "1") (pinfunction "1_1") (pintype "passive"))
    )
    (net (code "24") (name "BA1") (class "Default")
      (node (ref "IC1") (pin "21") (pinfunction "BA1_21") (pintype "bidirectional"))
      (node (ref "R30") (pin "1") (pinfunction "1_1") (pintype "passive"))
    )
    (net (code "25") (name "CAN0_N") (class "Default")
      (node (ref "J1") (pin "6") (pinfunction "6_6") (pintype "passive"))
      (node (ref "J2") (pin "6") (pinfunction "6_6") (pintype "passive"))
      (node (ref "R26999") (pin "1") (pinfunction "1_1") (pintype "passive"))
      (node (ref "U7") (pin "6") (pinfunction "CANL_6") (pintype "bidirectional"))
    )
    (net (code "26") (name "CAN0_P") (class "Default")
      (node (ref "J1") (pin "4") (pinfunction "4_4") (pintype "passive"))
      (node (ref "J2") (pin "4") (pinfunction "4_4") (pintype "passive"))
      (node (ref "R26999") (pin "2") (pinfunction "2_2") (pintype "passive"))
      (node (ref "U7") (pin "7") (pinfunction "CANH_7") (pintype "bidirectional"))
    )
    (net (code "27") (name "CAN1_N") (class "Default")
      (node (ref "J1") (pin "5") (pinfunction "5_5") (pintype "passive"))
      (node (ref "J2") (pin "5") (pinfunction "5_5") (pintype "passive"))
      (node (ref "R39") (pin "1") (pinfunction "1_1") (pintype "passive"))
      (node (ref "U2") (pin "6") (pinfunction "CANL_6") (pintype "bidirectional"))
    )
    (net (code "28") (name "CAN1_P") (class "Default")
      (node (ref "J1") (pin "3") (pinfunction "3_3") (pintype "passive"))
      (node (ref "J2") (pin "3") (pinfunction "3_3") (pintype "passive"))
      (node (ref "R39") (pin "2") (pinfunction "2_2") (pintype "passive"))
      (node (ref "U2") (pin "7") (pinfunction "CANH_7") (pintype "bidirectional"))
    )
    (net (code "29") (name "CAS") (class "Default")
      (node (ref "IC1") (pin "17") (pinfunction "~{CAS}_17") (pintype "bidirectional"))
      (node (ref "R35") (pin "1") (pinfunction "1_1") (pintype "passive"))
    )
    (net (code "30") (name "CDCK") (class "Default")
      (node (ref "IC1") (pin "38") (pinfunction "CLK_38") (pintype "bidirectional"))
      (node (ref "R31") (pin "1") (pinfunction "1_1") (pintype "passive"))
    )
    (net (code "31") (name "CDCKE") (class "Default")
      (node (ref "IC1") (pin "37") (pinfunction "CKE_37") (pintype "bidirectional"))
      (node (ref "R32") (pin "1") (pinfunction "1_1") (pintype "passive"))
    )
    (net (code "32") (name "CDCS") (class "Default")
      (node (ref "IC1") (pin "19") (pinfunction "~{CS}_19") (pintype "bidirectional"))
      (node (ref "R33") (pin "1") (pinfunction "1_1") (pintype "passive"))
    )
    (net (code "33") (name "DETECT_A") (class "Default")
      (node (ref "J1") (pin "10") (pinfunction "10_10") (pintype "passive"))
    )
    (net (code "34") (name "DETECT_B") (class "Default")
      (node (ref "J2") (pin "10") (pinfunction "10_10") (pintype "passive"))
    )
    (net (code "35") (name "DQ0") (class "Default")
      (node (ref "IC1") (pin "2") (pinfunction "DQ0_2") (pintype "bidirectional"))
      (node (ref "R13") (pin "1") (pinfunction "1_1") (pintype "passive"))
    )
    (net (code "36") (name "DQ1") (class "Default")
      (node (ref "IC1") (pin "4") (pinfunction "DQ1_4") (pintype "bidirectional"))
      (node (ref "R14") (pin "1") (pinfunction "1_1") (pintype "passive"))
    )
    (net (code "37") (name "DQ2") (class "Default")
      (node (ref "IC1") (pin "5") (pinfunction "DQ2_5") (pintype "bidirectional"))
      (node (ref "R15") (pin "1") (pinfunction "1_1") (pintype "passive"))
    )
    (net (code "38") (name "DQ3") (class "Default")
      (node (ref "IC1") (pin "7") (pinfunction "DQ3_7") (pintype "bidirectional"))
      (node (ref "R16") (pin "1") (pinfunction "1_1") (pintype "passive"))
    )
    (net (code "39") (name "DQ4") (class "Default")
      (node (ref "IC1") (pin "8") (pinfunction "DQ4_8") (pintype "bidirectional"))
      (node (ref "R17") (pin "1") (pinfunction "1_1") (pintype "passive"))
    )
    (net (code "40") (name "DQ5") (class "Default")
      (node (ref "IC1") (pin "10") (pinfunction "DQ5_10") (pintype "bidirectional"))
      (node (ref "R18") (pin "1") (pinfunction "1_1") (pintype "passive"))
    )
    (net (code "41") (name "DQ6") (class "Default")
      (node (ref "IC1") (pin "11") (pinfunction "DQ6_11") (pintype "bidirectional"))
      (node (ref "R19") (pin "1") (pinfunction "1_1") (pintype "passive"))
    )
    (net (code "42") (name "DQ7") (class "Default")
      (node (ref "IC1") (pin "13") (pinfunction "DQ7_13") (pintype "bidirectional"))
      (node (ref "R20") (pin "1") (pinfunction "1_1") (pintype "passive"))
    )
    (net (code "43") (name "DQ8") (class "Default")
      (node (ref "IC1") (pin "42") (pinfunction "DQ8_42") (pintype "bidirectional"))
      (node (ref "R21") (pin "1") (pinfunction "1_1") (pintype "passive"))
    )
    (net (code "44") (name "DQ9") (class "Default")
      (node (ref "IC1") (pin "44") (pinfunction "DQ9_44") (pintype "bidirectional"))
      (node (ref "R22") (pin "1") (pinfunction "1_1") (pintype "passive"))
    )
    (net (code "45") (name "DQ10") (class "Default")
      (node (ref "IC1") (pin "45") (pinfunction "DQ10_45") (pintype "bidirectional"))
      (node (ref "R23") (pin "1") (pinfunction "1_1") (pintype "passive"))
    )
    (net (code "46") (name "DQ11") (class "Default")
      (node (ref "IC1") (pin "47") (pinfunction "DQ11_47") (pintype "bidirectional"))
      (node (ref "R24") (pin "1") (pinfunction "1_1") (pintype "passive"))
    )
    (net (code "47") (name "DQ12") (class "Default")
      (node (ref "IC1") (pin "48") (pinfunction "DQ12_48") (pintype "bidirectional"))
      (node (ref "R25") (pin "1") (pinfunction "1_1") (pintype "passive"))
    )
    (net (code "48") (name "DQ13") (class "Default")
      (node (ref "IC1") (pin "50") (pinfunction "DQ13_50") (pintype "bidirectional"))
      (node (ref "R26") (pin "1") (pinfunction "1_1") (pintype "passive"))
    )
    (net (code "49") (name "DQ14") (class "Default")
      (node (ref "IC1") (pin "51") (pinfunction "DQ14_51") (pintype "bidirectional"))
      (node (ref "R27") (pin "1") (pinfunction "1_1") (pintype "passive"))
    )
    (net (code "50") (name "DQ15") (class "Default")
      (node (ref "IC1") (pin "53") (pinfunction "DQ15_53") (pintype "bidirectional"))
      (node (ref "R28") (pin "1") (pinfunction "1_1") (pintype "passive"))
    )
    (net (code "51") (name "DQMH") (class "Default")
      (node (ref "IC1") (pin "39") (pinfunction "DQMH_39") (pintype "bidirectional"))
      (node (ref "R38") (pin "1") (pinfunction "1_1") (pintype "passive"))
    )
    (net (code "52") (name "DQML") (class "Default")
      (node (ref "IC1") (pin "15") (pinfunction "DQML_15") (pintype "bidirectional"))
      (node (ref "R37") (pin "1") (pinfunction "1_1") (pintype "passive"))
    )
    (net (code "53") (name "ETH_RX+") (class "Default")
      (node (ref "J1") (pin "36") (pinfunction "36_36") (pintype "passive"))
      (node (ref "J2") (pin "36") (pinfunction "36_36") (pintype "passive"))
    )
    (net (code "54") (name "ETH_RX-") (class "Default")
      (node (ref "J1") (pin "38") (pinfunction "38_38") (pintype "passive"))
      (node (ref "J2") (pin "38") (pinfunction "38_38") (pintype "passive"))
    )
    (net (code "55") (name "ETH_TX+") (class "Default")
      (node (ref "J1") (pin "32") (pinfunction "32_32") (pintype "passive"))
      (node (ref "J2") (pin "32") (pinfunction "32_32") (pintype "passive"))
    )
    (net (code "56") (name "ETH_TX-") (class "Default")
      (node (ref "J1") (pin "34") (pinfunction "34_34") (pintype "passive"))
      (node (ref "J2") (pin "34") (pinfunction "34_34") (pintype "passive"))
    )
    (net (code "57") (name "GND") (class "Default")
      (node (ref "C1") (pin "2") (pinfunction "2_2") (pintype "passive"))
      (node (ref "C10") (pin "2") (pinfunction "2_2") (pintype "passive"))
      (node (ref "C11") (pin "2") (pinfunction "2_2") (pintype "passive"))
      (node (ref "C12") (pin "2") (pinfunction "2_2") (pintype "passive"))
      (node (ref "C13") (pin "2") (pinfunction "2_2") (pintype "passive"))
      (node (ref "C14") (pin "2") (pinfunction "2_2") (pintype "passive"))
      (node (ref "C15") (pin "2") (pinfunction "2_2") (pintype "passive"))
      (node (ref "C16") (pin "2") (pinfunction "2_2") (pintype "passive"))
      (node (ref "C17") (pin "2") (pinfunction "2_2") (pintype "passive"))
      (node (ref "C18") (pin "2") (pinfunction "2_2") (pintype "passive"))
      (node (ref "C19") (pin "2") (pinfunction "2_2") (pintype "passive"))
      (node (ref "C2") (pin "2") (pinfunction "2_2") (pintype "passive"))
      (node (ref "C20") (pin "2") (pinfunction "2_2") (pintype "passive"))
      (node (ref "C21") (pin "2") (pinfunction "2_2") (pintype "passive"))
      (node (ref "C22") (pin "2") (pinfunction "2_2") (pintype "passive"))
      (node (ref "C23") (pin "-") (pinfunction "-_-") (pintype "passive"))
      (node (ref "C24") (pin "-") (pinfunction "-_-") (pintype "passive"))
      (node (ref "C25") (pin "2") (pinfunction "2_2") (pintype "passive"))
      (node (ref "C26") (pin "2") (pinfunction "2_2") (pintype "passive"))
      (node (ref "C27") (pin "2") (pinfunction "2_2") (pintype "passive"))
      (node (ref "C28") (pin "2") (pinfunction "2_2") (pintype "passive"))
      (node (ref "C29") (pin "2") (pinfunction "2_2") (pintype "passive"))
      (node (ref "C3") (pin "2") (pinfunction "2_2") (pintype "passive"))
      (node (ref "C30") (pin "2") (pinfunction "2_2") (pintype "passive"))
      (node (ref "C4") (pin "2") (pinfunction "2_2") (pintype "passive"))
      (node (ref "C5") (pin "2") (pinfunction "2_2") (pintype "passive"))
      (node (ref "C6") (pin "2") (pinfunction "2_2") (pintype "passive"))
      (node (ref "C7") (pin "2") (pinfunction "2_2") (pintype "passive"))
      (node (ref "C8") (pin "2") (pinfunction "2_2") (pintype "passive"))
      (node (ref "C9") (pin "2") (pinfunction "2_2") (pintype "passive"))
      (node (ref "IC1") (pin "12") (pinfunction "VSSQ_2_12") (pintype "bidirectional"))
      (node (ref "IC1") (pin "28") (pinfunction "VSS_1_28") (pintype "bidirectional"))
      (node (ref "IC1") (pin "41") (pinfunction "VSS_2_41") (pintype "bidirectional"))
      (node (ref "IC1") (pin "46") (pinfunction "VSSQ_3_46") (pintype "bidirectional"))
      (node (ref "IC1") (pin "52") (pinfunction "VSSQ_4_52") (pintype "bidirectional"))
      (node (ref "IC1") (pin "54") (pinfunction "VSS_3_54") (pintype "bidirectional"))
      (node (ref "IC1") (pin "6") (pinfunction "VSSQ_1_6") (pintype "bidirectional"))
      (node (ref "IC2") (pin "1") (pinfunction "ADJ_1") (pintype "input"))
      (node (ref "IC3") (pin "2") (pinfunction "GND_2") (pintype "bidirectional"))
      (node (ref "J3") (pin "10") (pinfunction "10_10") (pintype "passive"))
      (node (ref "J3") (pin "12") (pinfunction "12_12") (pintype "passive"))
      (node (ref "J3") (pin "14") (pinfunction "14_14") (pintype "passive"))
      (node (ref "J3") (pin "16") (pinfunction "16_16") (pintype "passive"))
      (node (ref "J3") (pin "18") (pinfunction "18_18") (pintype "passive"))
      (node (ref "J3") (pin "2") (pinfunction "2_2") (pintype "passive"))
      (node (ref "J3") (pin "20") (pinfunction "20_20") (pintype "passive"))
      (node (ref "J3") (pin "22") (pinfunction "22_22") (pintype "passive"))
      (node (ref "J3") (pin "24") (pinfunction "24_24") (pintype "passive"))
      (node (ref "J3") (pin "26") (pinfunction "26_26") (pintype "passive"))
      (node (ref "J3") (pin "28") (pinfunction "28_28") (pintype "passive"))
      (node (ref "J3") (pin "30") (pinfunction "30_30") (pintype "passive"))
      (node (ref "J3") (pin "32") (pinfunction "32_32") (pintype "passive"))
      (node (ref "J3") (pin "34") (pinfunction "34_34") (pintype "passive"))
      (node (ref "J3") (pin "36") (pinfunction "36_36") (pintype "passive"))
      (node (ref "J3") (pin "38") (pinfunction "38_38") (pintype "passive"))
      (node (ref "J3") (pin "4") (pinfunction "4_4") (pintype "passive"))
      (node (ref "J3") (pin "40") (pinfunction "40_40") (pintype "passive"))
      (node (ref "J3") (pin "6") (pinfunction "6_6") (pintype "passive"))
      (node (ref "J3") (pin "8") (pinfunction "8_8") (pintype "passive"))
      (node (ref "J4") (pin "10") (pinfunction "10_10") (pintype "passive"))
      (node (ref "J4") (pin "12") (pinfunction "12_12") (pintype "passive"))
      (node (ref "J4") (pin "14") (pinfunction "14_14") (pintype "passive"))
      (node (ref "J4") (pin "16") (pinfunction "16_16") (pintype "passive"))
      (node (ref "J4") (pin "18") (pinfunction "18_18") (pintype "passive"))
      (node (ref "J4") (pin "2") (pinfunction "2_2") (pintype "passive"))
      (node (ref "J4") (pin "20") (pinfunction "20_20") (pintype "passive"))
      (node (ref "J4") (pin "22") (pinfunction "22_22") (pintype "passive"))
      (node (ref "J4") (pin "24") (pinfunction "24_24") (pintype "passive"))
      (node (ref "J4") (pin "26") (pinfunction "26_26") (pintype "passive"))
      (node (ref "J4") (pin "28") (pinfunction "28_28") (pintype "passive"))
      (node (ref "J4") (pin "30") (pinfunction "30_30") (pintype "passive"))
      (node (ref "J4") (pin "32") (pinfunction "32_32") (pintype "passive"))
      (node (ref "J4") (pin "34") (pinfunction "34_34") (pintype "passive"))
      (node (ref "J4") (pin "36") (pinfunction "36_36") (pintype "passive"))
      (node (ref "J4") (pin "38") (pinfunction "38_38") (pintype "passive"))
      (node (ref "J4") (pin "4") (pinfunction "4_4") (pintype "passive"))
      (node (ref "J4") (pin "40") (pinfunction "40_40") (pintype "passive"))
      (node (ref "J4") (pin "6") (pinfunction "6_6") (pintype "passive"))
      (node (ref "J4") (pin "8") (pinfunction "8_8") (pintype "passive"))
      (node (ref "J6") (pin "3") (pinfunction "3_GND_3") (pintype "passive"))
      (node (ref "J6") (pin "5") (pinfunction "5_GND_5") (pintype "passive"))
      (node (ref "J6") (pin "9") (pinfunction "9_GND_9") (pintype "passive"))
      (node (ref "R89999") (pin "2") (pinfunction "2_2") (pintype "passive"))
      (node (ref "U$5") (pin "6") (pinfunction "VSS_6") (pintype "power_in"))
      (node (ref "U$5") (pin "MT1") (pinfunction "GND_MT1") (pintype "power_in"))
      (node (ref "U$5") (pin "MT2") (pinfunction "GND1_MT2") (pintype "power_in"))
      (node (ref "U1") (pin "115") (pinfunction "GND_5_115") (pintype "passive"))
      (node (ref "U1") (pin "135") (pinfunction "GND_6_135") (pintype "passive"))
      (node (ref "U1") (pin "138") (pinfunction "GND_138") (pintype "passive"))
      (node (ref "U1") (pin "44") (pinfunction "GND_2_44") (pintype "passive"))
      (node (ref "U1") (pin "61") (pinfunction "GND_3_61") (pintype "passive"))
      (node (ref "U1") (pin "95") (pinfunction "GND_4_95") (pintype "passive"))
      (node (ref "U2") (pin "2") (pinfunction "GND_2") (pintype "bidirectional"))
      (node (ref "U3") (pin "1") (pinfunction "GND_1") (pintype "power_in"))
      (node (ref "U3") (pin "2") (pinfunction "RESV2_2") (pintype "passive"))
      (node (ref "U3") (pin "5") (pinfunction "RESV5_5") (pintype "passive"))
      (node (ref "U3") (pin "6") (pinfunction "RESV6_6") (pintype "passive"))
      (node (ref "U3") (pin "7") (pinfunction "GND_7") (pintype "power_in"))
      (node (ref "U4") (pin "4") (pinfunction "GND_4") (pintype "bidirectional"))
      (node (ref "U7") (pin "2") (pinfunction "GND_2") (pintype "bidirectional"))
    )
    (net (code "58") (name "I2C_SCL") (class "Default")
      (node (ref "J1") (pin "22") (pinfunction "22_22") (pintype "passive"))
      (node (ref "J2") (pin "22") (pinfunction "22_22") (pintype "passive"))
    )
    (net (code "59") (name "I2C_SDA") (class "Default")
      (node (ref "J1") (pin "20") (pinfunction "20_20") (pintype "passive"))
      (node (ref "J2") (pin "20") (pinfunction "20_20") (pintype "passive"))
    )
    (net (code "60") (name "Net-(L2-Pad1)") (class "Default")
      (node (ref "L2") (pin "1") (pinfunction "1_1") (pintype "passive"))
      (node (ref "R40") (pin "2") (pinfunction "2_2") (pintype "passive"))
    )
    (net (code "61") (name "Net-(U4-EN)") (class "Default")
      (node (ref "C28") (pin "1") (pinfunction "1_1") (pintype "passive"))
      (node (ref "R45") (pin "2") (pinfunction "2_2") (pintype "passive"))
      (node (ref "U4") (pin "7") (pinfunction "VREF2_7") (pintype "bidirectional"))
      (node (ref "U4") (pin "8") (pinfunction "EN_8") (pintype "bidirectional"))
    )
    (net (code "62") (name "PA0") (class "Default")
      (node (ref "R30") (pin "2") (pinfunction "2_2") (pintype "passive"))
      (node (ref "U1") (pin "102") (pinfunction "PA0_102") (pintype "bidirectional"))
    )
    (net (code "63") (name "PA1") (class "Default")
      (node (ref "U1") (pin "99") (pinfunction "PA1_99") (pintype "bidirectional"))
      (node (ref "U7") (pin "8") (pinfunction "STBY_8") (pintype "bidirectional"))
    )
    (net (code "64") (name "PA2") (class "Default")
      (node (ref "U1") (pin "93") (pinfunction "PA2_93") (pintype "bidirectional"))
      (node (ref "U2") (pin "8") (pinfunction "STBY_8") (pintype "bidirectional"))
    )
    (net (code "65") (name "PA3") (class "Default")
      (node (ref "R43") (pin "1") (pinfunction "1_1") (pintype "passive"))
      (node (ref "U1") (pin "91") (pinfunction "PA3_91") (pintype "bidirectional"))
      (node (ref "U4") (pin "5") (pinfunction "SDA2_5") (pintype "bidirectional"))
    )
    (net (code "66") (name "PA4") (class "Default")
      (node (ref "R44") (pin "1") (pinfunction "1_1") (pintype "passive"))
      (node (ref "U1") (pin "77") (pinfunction "PA4_77") (pintype "bidirectional"))
      (node (ref "U4") (pin "6") (pinfunction "SCL2_6") (pintype "bidirectional"))
    )
    (net (code "67") (name "PA5") (class "Default")
      (node (ref "U1") (pin "73") (pinfunction "PA5_73") (pintype "bidirectional"))
    )
    (net (code "68") (name "PA6") (class "Default")
      (node (ref "U1") (pin "114") (pinfunction "PA6_114") (pintype "bidirectional"))
    )
    (net (code "69") (name "PA7") (class "Default")
      (node (ref "U1") (pin "35") (pinfunction "PA7_35") (pintype "bidirectional"))
    )
    (net (code "70") (name "PA8") (class "Default")
      (node (ref "U1") (pin "36") (pinfunction "PA8_36") (pintype "bidirectional"))
    )
    (net (code "71") (name "PA9") (class "Default")
      (node (ref "U1") (pin "75") (pinfunction "PA9_75") (pintype "bidirectional"))
    )
    (net (code "72") (name "PA10") (class "Default")
      (node (ref "U1") (pin "66") (pinfunction "PA10_66") (pintype "bidirectional"))
    )
    (net (code "73") (name "PA11") (class "Default")
      (node (ref "U1") (pin "64") (pinfunction "PA11_64") (pintype "bidirectional"))
    )
    (net (code "74") (name "PA12") (class "Default")
      (node (ref "U1") (pin "68") (pinfunction "PA12_68") (pintype "bidirectional"))
    )
    (net (code "75") (name "PA13") (class "Default")
      (node (ref "U1") (pin "42") (pinfunction "PA13_42") (pintype "bidirectional"))
    )
    (net (code "76") (name "PA14") (class "Default")
      (node (ref "U1") (pin "51") (pinfunction "PA14_51") (pintype "bidirectional"))
    )
    (net (code "77") (name "PA15") (class "Default")
      (node (ref "R27") (pin "2") (pinfunction "2_2") (pintype "passive"))
      (node (ref "U1") (pin "49") (pinfunction "PA15_49") (pintype "bidirectional"))
    )
    (net (code "78") (name "PA16") (class "Default")
      (node (ref "R28") (pin "2") (pinfunction "2_2") (pintype "passive"))
      (node (ref "U1") (pin "45") (pinfunction "PA16_45") (pintype "bidirectional"))
    )
    (net (code "79") (name "PA17") (class "Default")
      (node (ref "U1") (pin "25") (pinfunction "PA17_25") (pintype "bidirectional"))
    )
    (net (code "80") (name "PA18") (class "Default")
      (node (ref "U1") (pin "24") (pinfunction "PA18_24") (pintype "bidirectional"))
    )
    (net (code "81") (name "PA19") (class "Default")
      (node (ref "U1") (pin "23") (pinfunction "PA19_23") (pintype "bidirectional"))
    )
    (net (code "82") (name "PA20") (class "Default")
      (node (ref "R29") (pin "2") (pinfunction "2_2") (pintype "passive"))
      (node (ref "U1") (pin "22") (pinfunction "PA20_22") (pintype "bidirectional"))
    )
    (net (code "83") (name "PA21") (class "Default")
      (node (ref "U1") (pin "32") (pinfunction "PA21_32") (pintype "bidirectional"))
    )
    (net (code "84") (name "PA22") (class "Default")
      (node (ref "U1") (pin "37") (pinfunction "PA22_37") (pintype "bidirectional"))
    )
    (net (code "85") (name "PA23") (class "Default")
      (node (ref "U1") (pin "46") (pinfunction "PA23_46") (pintype "bidirectional"))
    )
    (net (code "86") (name "PA24") (class "Default")
      (node (ref "U1") (pin "56") (pinfunction "PA24_56") (pintype "bidirectional"))
    )
    (net (code "87") (name "PA25") (class "Default")
      (node (ref "U$5") (pin "5") (pinfunction "SCLK_5") (pintype "input"))
      (node (ref "U1") (pin "59") (pinfunction "PA25_59") (pintype "bidirectional"))
    )
    (net (code "88") (name "PA26") (class "Default")
      (node (ref "U$5") (pin "1") (pinfunction "DAT2_1") (pintype "bidirectional"))
      (node (ref "U1") (pin "62") (pinfunction "PA26_62") (pintype "bidirectional"))
    )
    (net (code "89") (name "PA27") (class "Default")
      (node (ref "U$5") (pin "2") (pinfunction "CS_2") (pintype "input"))
      (node (ref "U1") (pin "70") (pinfunction "PA27_70") (pintype "bidirectional"))
    )
    (net (code "90") (name "PA28") (class "Default")
      (node (ref "U$5") (pin "3") (pinfunction "DATA_IN_3") (pintype "input"))
      (node (ref "U1") (pin "112") (pinfunction "PA28_112") (pintype "bidirectional"))
    )
    (net (code "91") (name "PA29") (class "Default")
      (node (ref "U1") (pin "129") (pinfunction "PA29_129") (pintype "bidirectional"))
    )
    (net (code "92") (name "PA30") (class "Default")
      (node (ref "U$5") (pin "7") (pinfunction "DATA_OUT_7") (pintype "output"))
      (node (ref "U1") (pin "116") (pinfunction "PA30_116") (pintype "bidirectional"))
    )
    (net (code "93") (name "PA31") (class "Default")
      (node (ref "U$5") (pin "8") (pinfunction "DAT1_8") (pintype "bidirectional"))
      (node (ref "U1") (pin "118") (pinfunction "PA31_118") (pintype "bidirectional"))
    )
    (net (code "94") (name "PB0") (class "Default")
      (node (ref "U1") (pin "21") (pinfunction "PB0_21") (pintype "bidirectional"))
    )
    (net (code "95") (name "PB1") (class "Default")
      (node (ref "U1") (pin "20") (pinfunction "PB1_20") (pintype "bidirectional"))
    )
    (net (code "96") (name "PB2") (class "Default")
      (node (ref "U1") (pin "26") (pinfunction "PB2_26") (pintype "bidirectional"))
      (node (ref "U7") (pin "1") (pinfunction "TXD_1") (pintype "bidirectional"))
    )
    (net (code "97") (name "PB3") (class "Default")
      (node (ref "U1") (pin "31") (pinfunction "PB3_31") (pintype "bidirectional"))
      (node (ref "U7") (pin "4") (pinfunction "RXD_4") (pintype "bidirectional"))
    )
    (net (code "98") (name "PB4") (class "Default")
      (node (ref "U1") (pin "105") (pinfunction "PB4_105") (pintype "bidirectional"))
    )
    (net (code "99") (name "PB5") (class "Default")
      (node (ref "U1") (pin "109") (pinfunction "PB5_109") (pintype "bidirectional"))
    )
    (net (code "100") (name "PB6") (class "Default")
      (node (ref "U1") (pin "79") (pinfunction "PB6_79") (pintype "bidirectional"))
    )
    (net (code "101") (name "PB7") (class "Default")
      (node (ref "U1") (pin "89") (pinfunction "PB7_89") (pintype "bidirectional"))
    )
    (net (code "102") (name "PB8") (class "Default")
      (node (ref "U1") (pin "141") (pinfunction "PB8_141") (pintype "bidirectional"))
    )
    (net (code "103") (name "PB9") (class "Default")
      (node (ref "U1") (pin "142") (pinfunction "PB9_142") (pintype "bidirectional"))
    )
    (net (code "104") (name "PB12") (class "Default")
      (node (ref "U1") (pin "87") (pinfunction "PB12_87") (pintype "bidirectional"))
    )
    (net (code "105") (name "PB13") (class "Default")
      (node (ref "U1") (pin "144") (pinfunction "PB13_144") (pintype "bidirectional"))
    )
    (net (code "106") (name "PC0") (class "Default")
      (node (ref "R13") (pin "2") (pinfunction "2_2") (pintype "passive"))
      (node (ref "U1") (pin "11") (pinfunction "PC0_11") (pintype "bidirectional"))
    )
    (net (code "107") (name "PC1") (class "Default")
      (node (ref "R14") (pin "2") (pinfunction "2_2") (pintype "passive"))
      (node (ref "U1") (pin "38") (pinfunction "PC1_38") (pintype "bidirectional"))
    )
    (net (code "108") (name "PC2") (class "Default")
      (node (ref "R15") (pin "2") (pinfunction "2_2") (pintype "passive"))
      (node (ref "U1") (pin "39") (pinfunction "PC2_39") (pintype "bidirectional"))
    )
    (net (code "109") (name "PC3") (class "Default")
      (node (ref "R16") (pin "2") (pinfunction "2_2") (pintype "passive"))
      (node (ref "U1") (pin "40") (pinfunction "PC3_40") (pintype "bidirectional"))
    )
    (net (code "110") (name "PC4") (class "Default")
      (node (ref "R17") (pin "2") (pinfunction "2_2") (pintype "passive"))
      (node (ref "U1") (pin "41") (pinfunction "PC4_41") (pintype "bidirectional"))
    )
    (net (code "111") (name "PC5") (class "Default")
      (node (ref "R18") (pin "2") (pinfunction "2_2") (pintype "passive"))
      (node (ref "U1") (pin "58") (pinfunction "PC5_58") (pintype "bidirectional"))
    )
    (net (code "112") (name "PC6") (class "Default")
      (node (ref "R19") (pin "2") (pinfunction "2_2") (pintype "passive"))
      (node (ref "U1") (pin "54") (pinfunction "PC6_54") (pintype "bidirectional"))
    )
    (net (code "113") (name "PC7") (class "Default")
      (node (ref "R20") (pin "2") (pinfunction "2_2") (pintype "passive"))
      (node (ref "U1") (pin "48") (pinfunction "PC7_48") (pintype "bidirectional"))
    )
    (net (code "114") (name "PC8") (class "Default")
      (node (ref "U1") (pin "82") (pinfunction "PC8_82") (pintype "bidirectional"))
    )
    (net (code "115") (name "PC9") (class "Default")
      (node (ref "U1") (pin "86") (pinfunction "PC9_86") (pintype "bidirectional"))
    )
    (net (code "116") (name "PC10") (class "Default")
      (node (ref "U1") (pin "90") (pinfunction "PC10_90") (pintype "bidirectional"))
    )
    (net (code "117") (name "PC11") (class "Default")
      (node (ref "U1") (pin "94") (pinfunction "PC11_94") (pintype "bidirectional"))
    )
    (net (code "118") (name "PC12") (class "Default")
      (node (ref "U1") (pin "17") (pinfunction "PC12_17") (pintype "bidirectional"))
      (node (ref "U2") (pin "4") (pinfunction "RXD_4") (pintype "bidirectional"))
    )
    (net (code "119") (name "PC13") (class "Default")
      (node (ref "U1") (pin "19") (pinfunction "PC13_19") (pintype "bidirectional"))
    )
    (net (code "120") (name "PC14") (class "Default")
      (node (ref "U1") (pin "97") (pinfunction "PC14_97") (pintype "bidirectional"))
      (node (ref "U2") (pin "1") (pinfunction "TXD_1") (pintype "bidirectional"))
    )
    (net (code "121") (name "PC15") (class "Default")
      (node (ref "R33") (pin "2") (pinfunction "2_2") (pintype "passive"))
      (node (ref "U1") (pin "18") (pinfunction "PC15_18") (pintype "bidirectional"))
    )
    (net (code "122") (name "PC16") (class "Default")
      (node (ref "U1") (pin "100") (pinfunction "PC16_100") (pintype "bidirectional"))
    )
    (net (code "123") (name "PC17") (class "Default")
      (node (ref "U1") (pin "103") (pinfunction "PC17_103") (pintype "bidirectional"))
    )
    (net (code "124") (name "PC18") (class "Default")
      (node (ref "R37") (pin "2") (pinfunction "2_2") (pintype "passive"))
      (node (ref "U1") (pin "111") (pinfunction "PC18_111") (pintype "bidirectional"))
    )
    (net (code "125") (name "PC19") (class "Default")
      (node (ref "U1") (pin "117") (pinfunction "PC19_117") (pintype "bidirectional"))
    )
    (net (code "126") (name "PC20") (class "Default")
      (node (ref "R1") (pin "2") (pinfunction "2_2") (pintype "passive"))
      (node (ref "U1") (pin "120") (pinfunction "PC20_120") (pintype "bidirectional"))
    )
    (net (code "127") (name "PC21") (class "Default")
      (node (ref "R2") (pin "2") (pinfunction "2_2") (pintype "passive"))
      (node (ref "U1") (pin "122") (pinfunction "PC21_122") (pintype "bidirectional"))
    )
    (net (code "128") (name "PC22") (class "Default")
      (node (ref "R3") (pin "2") (pinfunction "2_2") (pintype "passive"))
      (node (ref "U1") (pin "124") (pinfunction "PC22_124") (pintype "bidirectional"))
    )
    (net (code "129") (name "PC23") (class "Default")
      (node (ref "R4") (pin "2") (pinfunction "2_2") (pintype "passive"))
      (node (ref "U1") (pin "127") (pinfunction "PC23_127") (pintype "bidirectional"))
    )
    (net (code "130") (name "PC24") (class "Default")
      (node (ref "R5") (pin "2") (pinfunction "2_2") (pintype "passive"))
      (node (ref "U1") (pin "130") (pinfunction "PC24_130") (pintype "bidirectional"))
    )
    (net (code "131") (name "PC25") (class "Default")
      (node (ref "R6") (pin "2") (pinfunction "2_2") (pintype "passive"))
      (node (ref "U1") (pin "133") (pinfunction "PC25_133") (pintype "bidirectional"))
    )
    (net (code "132") (name "PC26") (class "Default")
      (node (ref "R7") (pin "2") (pinfunction "2_2") (pintype "passive"))
      (node (ref "U1") (pin "13") (pinfunction "PC26_13") (pintype "bidirectional"))
    )
    (net (code "133") (name "PC27") (class "Default")
      (node (ref "R8") (pin "2") (pinfunction "2_2") (pintype "passive"))
      (node (ref "U1") (pin "12") (pinfunction "PC27_12") (pintype "bidirectional"))
    )
    (net (code "134") (name "PC28") (class "Default")
      (node (ref "R9") (pin "2") (pinfunction "2_2") (pintype "passive"))
      (node (ref "U1") (pin "76") (pinfunction "PC28_76") (pintype "bidirectional"))
    )
    (net (code "135") (name "PC29") (class "Default")
      (node (ref "R10") (pin "2") (pinfunction "2_2") (pintype "passive"))
      (node (ref "U1") (pin "16") (pinfunction "PC29_16") (pintype "bidirectional"))
    )
    (net (code "136") (name "PC30") (class "Default")
      (node (ref "R11") (pin "2") (pinfunction "2_2") (pintype "passive"))
      (node (ref "U1") (pin "15") (pinfunction "PC30_15") (pintype "bidirectional"))
    )
    (net (code "137") (name "PC31") (class "Default")
      (node (ref "R12") (pin "2") (pinfunction "2_2") (pintype "passive"))
      (node (ref "U1") (pin "14") (pinfunction "PC31_14") (pintype "bidirectional"))
    )
    (net (code "138") (name "PD0") (class "Default")
      (node (ref "U1") (pin "1") (pinfunction "PD0_1") (pintype "bidirectional"))
    )
    (net (code "139") (name "PD1") (class "Default")
      (node (ref "U1") (pin "132") (pinfunction "PD1_132") (pintype "bidirectional"))
    )
    (net (code "140") (name "PD2") (class "Default")
      (node (ref "U1") (pin "131") (pinfunction "PD2_131") (pintype "bidirectional"))
    )
    (net (code "141") (name "PD3") (class "Default")
      (node (ref "U1") (pin "128") (pinfunction "PD3_128") (pintype "bidirectional"))
    )
    (net (code "142") (name "PD4") (class "Default")
      (node (ref "U1") (pin "126") (pinfunction "PD4_126") (pintype "bidirectional"))
    )
    (net (code "143") (name "PD5") (class "Default")
      (node (ref "U1") (pin "125") (pinfunction "PD5_125") (pintype "bidirectional"))
    )
    (net (code "144") (name "PD6") (class "Default")
      (node (ref "U1") (pin "121") (pinfunction "PD6_121") (pintype "bidirectional"))
    )
    (net (code "145") (name "PD7") (class "Default")
      (node (ref "U1") (pin "119") (pinfunction "PD7_119") (pintype "bidirectional"))
    )
    (net (code "146") (name "PD8") (class "Default")
      (node (ref "U1") (pin "113") (pinfunction "PD8_113") (pintype "bidirectional"))
    )
    (net (code "147") (name "PD9") (class "Default")
      (node (ref "U1") (pin "110") (pinfunction "PD9_110") (pintype "bidirectional"))
    )
    (net (code "148") (name "PD10") (class "Default")
      (node (ref "U1") (pin "101") (pinfunction "PD10_101") (pintype "bidirectional"))
    )
    (net (code "149") (name "PD11") (class "Default")
      (node (ref "U1") (pin "98") (pinfunction "PD11_98") (pintype "bidirectional"))
    )
    (net (code "150") (name "PD12") (class "Default")
      (node (ref "U1") (pin "92") (pinfunction "PD12_92") (pintype "bidirectional"))
    )
    (net (code "151") (name "PD13") (class "Default")
      (node (ref "U1") (pin "88") (pinfunction "PD13_88") (pintype "bidirectional"))
    )
    (net (code "152") (name "PD14") (class "Default")
      (node (ref "R32") (pin "2") (pinfunction "2_2") (pintype "passive"))
      (node (ref "U1") (pin "84") (pinfunction "PD14_84") (pintype "bidirectional"))
    )
    (net (code "153") (name "PD15") (class "Default")
      (node (ref "R38") (pin "2") (pinfunction "2_2") (pintype "passive"))
      (node (ref "U1") (pin "106") (pinfunction "PD15_106") (pintype "bidirectional"))
    )
    (net (code "154") (name "PD16") (class "Default")
      (node (ref "R34") (pin "2") (pinfunction "2_2") (pintype "passive"))
      (node (ref "U1") (pin "78") (pinfunction "PD16_78") (pintype "bidirectional"))
    )
    (net (code "155") (name "PD17") (class "Default")
      (node (ref "R35") (pin "2") (pinfunction "2_2") (pintype "passive"))
      (node (ref "U1") (pin "74") (pinfunction "PD17_74") (pintype "bidirectional"))
    )
    (net (code "156") (name "PD18") (class "Default")
      (node (ref "U1") (pin "69") (pinfunction "PD18_69") (pintype "bidirectional"))
    )
    (net (code "157") (name "PD19") (class "Default")
      (node (ref "U1") (pin "67") (pinfunction "PD19_67") (pintype "bidirectional"))
    )
    (net (code "158") (name "PD20") (class "Default")
      (node (ref "U1") (pin "65") (pinfunction "PD20_65") (pintype "bidirectional"))
    )
    (net (code "159") (name "PD21") (class "Default")
      (node (ref "U1") (pin "63") (pinfunction "PD21_63") (pintype "bidirectional"))
    )
    (net (code "160") (name "PD22") (class "Default")
      (node (ref "U1") (pin "60") (pinfunction "PD22_60") (pintype "bidirectional"))
    )
    (net (code "161") (name "PD23") (class "Default")
      (node (ref "R31") (pin "2") (pinfunction "2_2") (pintype "passive"))
      (node (ref "U1") (pin "57") (pinfunction "PD23_57") (pintype "bidirectional"))
    )
    (net (code "162") (name "PD24") (class "Default")
      (node (ref "U1") (pin "55") (pinfunction "PD24_55") (pintype "bidirectional"))
    )
    (net (code "163") (name "PD25") (class "Default")
      (node (ref "U1") (pin "52") (pinfunction "PD25_52") (pintype "bidirectional"))
    )
    (net (code "164") (name "PD26") (class "Default")
      (node (ref "U1") (pin "53") (pinfunction "PD26_53") (pintype "bidirectional"))
    )
    (net (code "165") (name "PD27") (class "Default")
      (node (ref "U1") (pin "47") (pinfunction "PD27_47") (pintype "bidirectional"))
    )
    (net (code "166") (name "PD28") (class "Default")
      (node (ref "U1") (pin "71") (pinfunction "PD28_71") (pintype "bidirectional"))
    )
    (net (code "167") (name "PD29") (class "Default")
      (node (ref "R36") (pin "2") (pinfunction "2_2") (pintype "passive"))
      (node (ref "U1") (pin "108") (pinfunction "PD29_108") (pintype "bidirectional"))
    )
    (net (code "168") (name "PD30") (class "Default")
      (node (ref "U1") (pin "34") (pinfunction "PD30_34") (pintype "bidirectional"))
    )
    (net (code "169") (name "PD31") (class "Default")
      (node (ref "U1") (pin "2") (pinfunction "PD31_2") (pintype "bidirectional"))
    )
    (net (code "170") (name "PE0") (class "Default")
      (node (ref "R21") (pin "2") (pinfunction "2_2") (pintype "passive"))
      (node (ref "U1") (pin "4") (pinfunction "PE0_4") (pintype "bidirectional"))
    )
    (net (code "171") (name "PE1") (class "Default")
      (node (ref "R22") (pin "2") (pinfunction "2_2") (pintype "passive"))
      (node (ref "U1") (pin "6") (pinfunction "PE1_6") (pintype "bidirectional"))
    )
    (net (code "172") (name "PE2") (class "Default")
      (node (ref "R23") (pin "2") (pinfunction "2_2") (pintype "passive"))
      (node (ref "U1") (pin "7") (pinfunction "PE2_7") (pintype "bidirectional"))
    )
    (net (code "173") (name "PE3") (class "Default")
      (node (ref "R24") (pin "2") (pinfunction "2_2") (pintype "passive"))
      (node (ref "U1") (pin "10") (pinfunction "PE3_10") (pintype "bidirectional"))
    )
    (net (code "174") (name "PE4") (class "Default")
      (node (ref "R25") (pin "2") (pinfunction "2_2") (pintype "passive"))
      (node (ref "U1") (pin "27") (pinfunction "PE4_27") (pintype "bidirectional"))
    )
    (net (code "175") (name "PE5") (class "Default")
      (node (ref "R26") (pin "2") (pinfunction "2_2") (pintype "passive"))
      (node (ref "U1") (pin "28") (pinfunction "PE5_28") (pintype "bidirectional"))
    )
    (net (code "176") (name "P_GOOD") (class "Default")
      (node (ref "J3") (pin "39") (pinfunction "39_39") (pintype "passive"))
      (node (ref "J4") (pin "39") (pinfunction "39_39") (pintype "passive"))
    )
    (net (code "177") (name "RAS") (class "Default")
      (node (ref "IC1") (pin "18") (pinfunction "~{RAS}_18") (pintype "bidirectional"))
      (node (ref "R34") (pin "1") (pinfunction "1_1") (pintype "passive"))
    )
    (net (code "178") (name "RESET") (class "Default")
      (node (ref "J6") (pin "10") (pinfunction "10_RESET_10") (pintype "passive"))
    )
    (net (code "179") (name "RFU_9") (class "Default")
      (node (ref "J1") (pin "9") (pinfunction "9_9") (pintype "passive"))
      (node (ref "J2") (pin "9") (pinfunction "9_9") (pintype "passive"))
    )
    (net (code "180") (name "RFU_11") (class "Default")
      (node (ref "J1") (pin "11") (pinfunction "11_11") (pintype "passive"))
      (node (ref "J2") (pin "11") (pinfunction "11_11") (pintype "passive"))
    )
    (net (code "181") (name "RFU_13") (class "Default")
      (node (ref "J1") (pin "13") (pinfunction "13_13") (pintype "passive"))
      (node (ref "J2") (pin "13") (pinfunction "13_13") (pintype "passive"))
    )
    (net (code "182") (name "RFU_15") (class "Default")
      (node (ref "J1") (pin "15") (pinfunction "15_15") (pintype "passive"))
      (node (ref "J2") (pin "15") (pinfunction "15_15") (pintype "passive"))
    )
    (net (code "183") (name "RFU_17") (class "Default")
      (node (ref "J1") (pin "17") (pinfunction "17_17") (pintype "passive"))
      (node (ref "J2") (pin "17") (pinfunction "17_17") (pintype "passive"))
    )
    (net (code "184") (name "RFU_19") (class "Default")
      (node (ref "J1") (pin "19") (pinfunction "19_19") (pintype "passive"))
      (node (ref "J2") (pin "19") (pinfunction "19_19") (pintype "passive"))
    )
    (net (code "185") (name "RFU_21") (class "Default")
      (node (ref "J1") (pin "21") (pinfunction "21_21") (pintype "passive"))
      (node (ref "J2") (pin "21") (pinfunction "21_21") (pintype "passive"))
    )
    (net (code "186") (name "RFU_23") (class "Default")
      (node (ref "J1") (pin "23") (pinfunction "23_23") (pintype "passive"))
      (node (ref "J2") (pin "23") (pinfunction "23_23") (pintype "passive"))
    )
    (net (code "187") (name "RFU_25") (class "Default")
      (node (ref "J1") (pin "25") (pinfunction "25_25") (pintype "passive"))
      (node (ref "J2") (pin "25") (pinfunction "25_25") (pintype "passive"))
    )
    (net (code "188") (name "RFU_27") (class "Default")
      (node (ref "J1") (pin "27") (pinfunction "27_27") (pintype "passive"))
      (node (ref "J2") (pin "27") (pinfunction "27_27") (pintype "passive"))
    )
    (net (code "189") (name "RFU_29") (class "Default")
      (node (ref "J1") (pin "29") (pinfunction "29_29") (pintype "passive"))
      (node (ref "J2") (pin "29") (pinfunction "29_29") (pintype "passive"))
    )
    (net (code "190") (name "RFU_31") (class "Default")
      (node (ref "J1") (pin "31") (pinfunction "31_31") (pintype "passive"))
      (node (ref "J2") (pin "31") (pinfunction "31_31") (pintype "passive"))
    )
    (net (code "191") (name "RFU_33") (class "Default")
      (node (ref "J1") (pin "33") (pinfunction "33_33") (pintype "passive"))
      (node (ref "J2") (pin "33") (pinfunction "33_33") (pintype "passive"))
    )
    (net (code "192") (name "RFU_35") (class "Default")
      (node (ref "J1") (pin "35") (pinfunction "35_35") (pintype "passive"))
      (node (ref "J2") (pin "35") (pinfunction "35_35") (pintype "passive"))
    )
    (net (code "193") (name "RFU_37") (class "Default")
      (node (ref "J1") (pin "37") (pinfunction "37_37") (pintype "passive"))
      (node (ref "J2") (pin "37") (pinfunction "37_37") (pintype "passive"))
    )
    (net (code "194") (name "RS485_D+") (class "Default")
      (node (ref "J1") (pin "26") (pinfunction "26_26") (pintype "passive"))
      (node (ref "J2") (pin "26") (pinfunction "26_26") (pintype "passive"))
    )
    (net (code "195") (name "RS485_D-") (class "Default")
      (node (ref "J1") (pin "28") (pinfunction "28_28") (pintype "passive"))
      (node (ref "J2") (pin "28") (pinfunction "28_28") (pintype "passive"))
    )
    (net (code "196") (name "SCL0_1V8") (class "Default")
      (node (ref "R42") (pin "1") (pinfunction "1_1") (pintype "passive"))
      (node (ref "U3") (pin "4") (pinfunction "SCL_4") (pintype "input"))
      (node (ref "U4") (pin "2") (pinfunction "SCL1_2") (pintype "bidirectional"))
    )
    (net (code "197") (name "SDA0_1V8") (class "Default")
      (node (ref "R41") (pin "1") (pinfunction "1_1") (pintype "passive"))
      (node (ref "U3") (pin "3") (pinfunction "SDA_3") (pintype "bidirectional"))
      (node (ref "U4") (pin "3") (pinfunction "SDA1_3") (pintype "bidirectional"))
    )
    (net (code "198") (name "SDWE") (class "Default")
      (node (ref "IC1") (pin "16") (pinfunction "~{WE}_16") (pintype "bidirectional"))
      (node (ref "R36") (pin "1") (pinfunction "1_1") (pintype "passive"))
    )
    (net (code "199") (name "SHIELD") (class "Default")
      (node (ref "J1") (pin "1") (pinfunction "1_1") (pintype "passive"))
      (node (ref "J1") (pin "18") (pinfunction "18_18") (pintype "passive"))
      (node (ref "J1") (pin "2") (pinfunction "2_2") (pintype "passive"))
      (node (ref "J1") (pin "24") (pinfunction "24_24") (pintype "passive"))
      (node (ref "J1") (pin "30") (pinfunction "30_30") (pintype "passive"))
      (node (ref "J1") (pin "39") (pinfunction "39_39") (pintype "passive"))
      (node (ref "J1") (pin "40") (pinfunction "40_40") (pintype "passive"))
      (node (ref "J1") (pin "7") (pinfunction "7_7") (pintype "passive"))
      (node (ref "J1") (pin "8") (pinfunction "8_8") (pintype "passive"))
      (node (ref "J2") (pin "1") (pinfunction "1_1") (pintype "passive"))
      (node (ref "J2") (pin "18") (pinfunction "18_18") (pintype "passive"))
      (node (ref "J2") (pin "2") (pinfunction "2_2") (pintype "passive"))
      (node (ref "J2") (pin "24") (pinfunction "24_24") (pintype "passive"))
      (node (ref "J2") (pin "30") (pinfunction "30_30") (pintype "passive"))
      (node (ref "J2") (pin "39") (pinfunction "39_39") (pintype "passive"))
      (node (ref "J2") (pin "40") (pinfunction "40_40") (pintype "passive"))
      (node (ref "J2") (pin "7") (pinfunction "7_7") (pintype "passive"))
      (node (ref "J2") (pin "8") (pinfunction "8_8") (pintype "passive"))
      (node (ref "R89999") (pin "1") (pinfunction "1_1") (pintype "passive"))
    )
    (net (code "200") (name "SPI_MISO") (class "Default")
      (node (ref "J1") (pin "12") (pinfunction "12_12") (pintype "passive"))
      (node (ref "J2") (pin "12") (pinfunction "12_12") (pintype "passive"))
    )
    (net (code "201") (name "SPI_MOSI") (class "Default")
      (node (ref "J1") (pin "14") (pinfunction "14_14") (pintype "passive"))
      (node (ref "J2") (pin "14") (pinfunction "14_14") (pintype "passive"))
    )
    (net (code "202") (name "SPI_SCK") (class "Default")
      (node (ref "J1") (pin "16") (pinfunction "16_16") (pintype "passive"))
      (node (ref "J2") (pin "16") (pinfunction "16_16") (pintype "passive"))
    )
    (net (code "203") (name "SWCLK") (class "Default")
      (node (ref "J6") (pin "4") (pinfunction "4_SWCLK_4") (pintype "passive"))
    )
    (net (code "204") (name "SWDIO") (class "Default")
      (node (ref "J6") (pin "2") (pinfunction "2SWDIO_2") (pintype "passive"))
    )
    (net (code "205") (name "VDDOUT") (class "Default")
      (node (ref "C17") (pin "1") (pinfunction "1_1") (pintype "passive"))
      (node (ref "C20") (pin "1") (pinfunction "1_1") (pintype "passive"))
      (node (ref "C22") (pin "1") (pinfunction "1_1") (pintype "passive"))
      (node (ref "C3") (pin "1") (pinfunction "1_1") (pintype "passive"))
      (node (ref "C4") (pin "1") (pinfunction "1_1") (pintype "passive"))
      (node (ref "C5") (pin "1") (pinfunction "1_1") (pintype "passive"))
      (node (ref "C6") (pin "1") (pinfunction "1_1") (pintype "passive"))
      (node (ref "C7") (pin "1") (pinfunction "1_1") (pintype "passive"))
      (node (ref "L1") (pin "1") (pinfunction "1_1") (pintype "passive"))
      (node (ref "U1") (pin "107") (pinfunction "VDDCORE_107") (pintype "power_in"))
      (node (ref "U1") (pin "139") (pinfunction "VDDTUMIC_139") (pintype "power_in"))
      (node (ref "U1") (pin "29") (pinfunction "VDDCORE_2_29") (pintype "power_in"))
      (node (ref "U1") (pin "3") (pinfunction "VDDOUT_3") (pintype "output"))
      (node (ref "U1") (pin "33") (pinfunction "VDDCORE_3_33") (pintype "power_in"))
      (node (ref "U1") (pin "50") (pinfunction "VDDCORE_4_50") (pintype "power_in"))
      (node (ref "U1") (pin "81") (pinfunction "VDDCORE_5_81") (pintype "power_in"))
    )
    (net (code "206") (name "VDDPLL") (class "Default")
      (node (ref "C15") (pin "1") (pinfunction "1_1") (pintype "passive"))
      (node (ref "L1") (pin "2") (pinfunction "2_2") (pintype "passive"))
      (node (ref "U1") (pin "123") (pinfunction "VDDPLL_123") (pintype "power_in"))
    )
    (net (code "207") (name "VDDPLLUSB") (class "Default")
      (node (ref "C16") (pin "1") (pinfunction "1_1") (pintype "passive"))
      (node (ref "L2") (pin "2") (pinfunction "2_2") (pintype "passive"))
      (node (ref "U1") (pin "143") (pinfunction "VDDPLLUSB_143") (pintype "power_in"))
    )
    (net (code "208") (name "VREFN") (class "Default")
      (node (ref "U1") (pin "8") (pinfunction "VREFN_8") (pintype "power_in"))
    )
    (net (code "209") (name "VREFP") (class "Default")
      (node (ref "U1") (pin "9") (pinfunction "VREFP_9") (pintype "power_in"))
    )
    (net (code "210") (name "unconnected-(IC1-NC_1-Pad36)") (class "Default")
      (node (ref "IC1") (pin "36") (pinfunction "NC_1_36") (pintype "bidirectional"))
    )
    (net (code "211") (name "unconnected-(IC1-NC_2-Pad40)") (class "Default")
      (node (ref "IC1") (pin "40") (pinfunction "NC_2_40") (pintype "bidirectional"))
    )
    (net (code "212") (name "unconnected-(J6-6_SWO-Pad6)") (class "Default")
      (node (ref "J6") (pin "6") (pinfunction "6_SWO_6") (pintype "passive"))
    )
    (net (code "213") (name "unconnected-(J6-7_NC-Pad7)") (class "Default")
      (node (ref "J6") (pin "7") (pinfunction "7_NC_7") (pintype "passive"))
    )
    (net (code "214") (name "unconnected-(J6-8_NC-Pad8)") (class "Default")
      (node (ref "J6") (pin "8") (pinfunction "8_NC_8") (pintype "passive"))
    )
    (net (code "215") (name "unconnected-(U$5-CARD_DETECT-PadCD1)") (class "Default")
      (node (ref "U$5") (pin "CD1") (pinfunction "CARD_DETECT_CD1") (pintype "passive"))
    )
    (net (code "216") (name "unconnected-(U$5-CARD_DETECT1-PadCD2)") (class "Default")
      (node (ref "U$5") (pin "CD2") (pinfunction "CARD_DETECT1_CD2") (pintype "passive"))
    )
    (net (code "217") (name "unconnected-(U1A-HSDM-Pad136)") (class "Default")
      (node (ref "U1") (pin "136") (pinfunction "HSDM_136") (pintype "passive"))
    )
    (net (code "218") (name "unconnected-(U1A-HSDP-Pad137)") (class "Default")
      (node (ref "U1") (pin "137") (pinfunction "HSDP_137") (pintype "passive"))
    )
    (net (code "219") (name "unconnected-(U1A-JTAGSEL-Pad104)") (class "Default")
      (node (ref "U1") (pin "104") (pinfunction "JTAGSEL_104") (pintype "passive"))
    )
    (net (code "220") (name "unconnected-(U1A-NRST-Pad83)") (class "Default")
      (node (ref "U1") (pin "83") (pinfunction "NRST_83") (pintype "passive"))
    )
    (net (code "221") (name "unconnected-(U1B-TST-Pad85)") (class "Default")
      (node (ref "U1") (pin "85") (pinfunction "TST_85") (pintype "passive"))
    )
    (net (code "222") (name "unconnected-(U1B-VBG-Pad140)") (class "Default")
      (node (ref "U1") (pin "140") (pinfunction "VBG_140") (pintype "passive"))
    )
  )
)
